# ISA_XILINX.net
KiCad netlist of a schematic drawn in Altium Designer
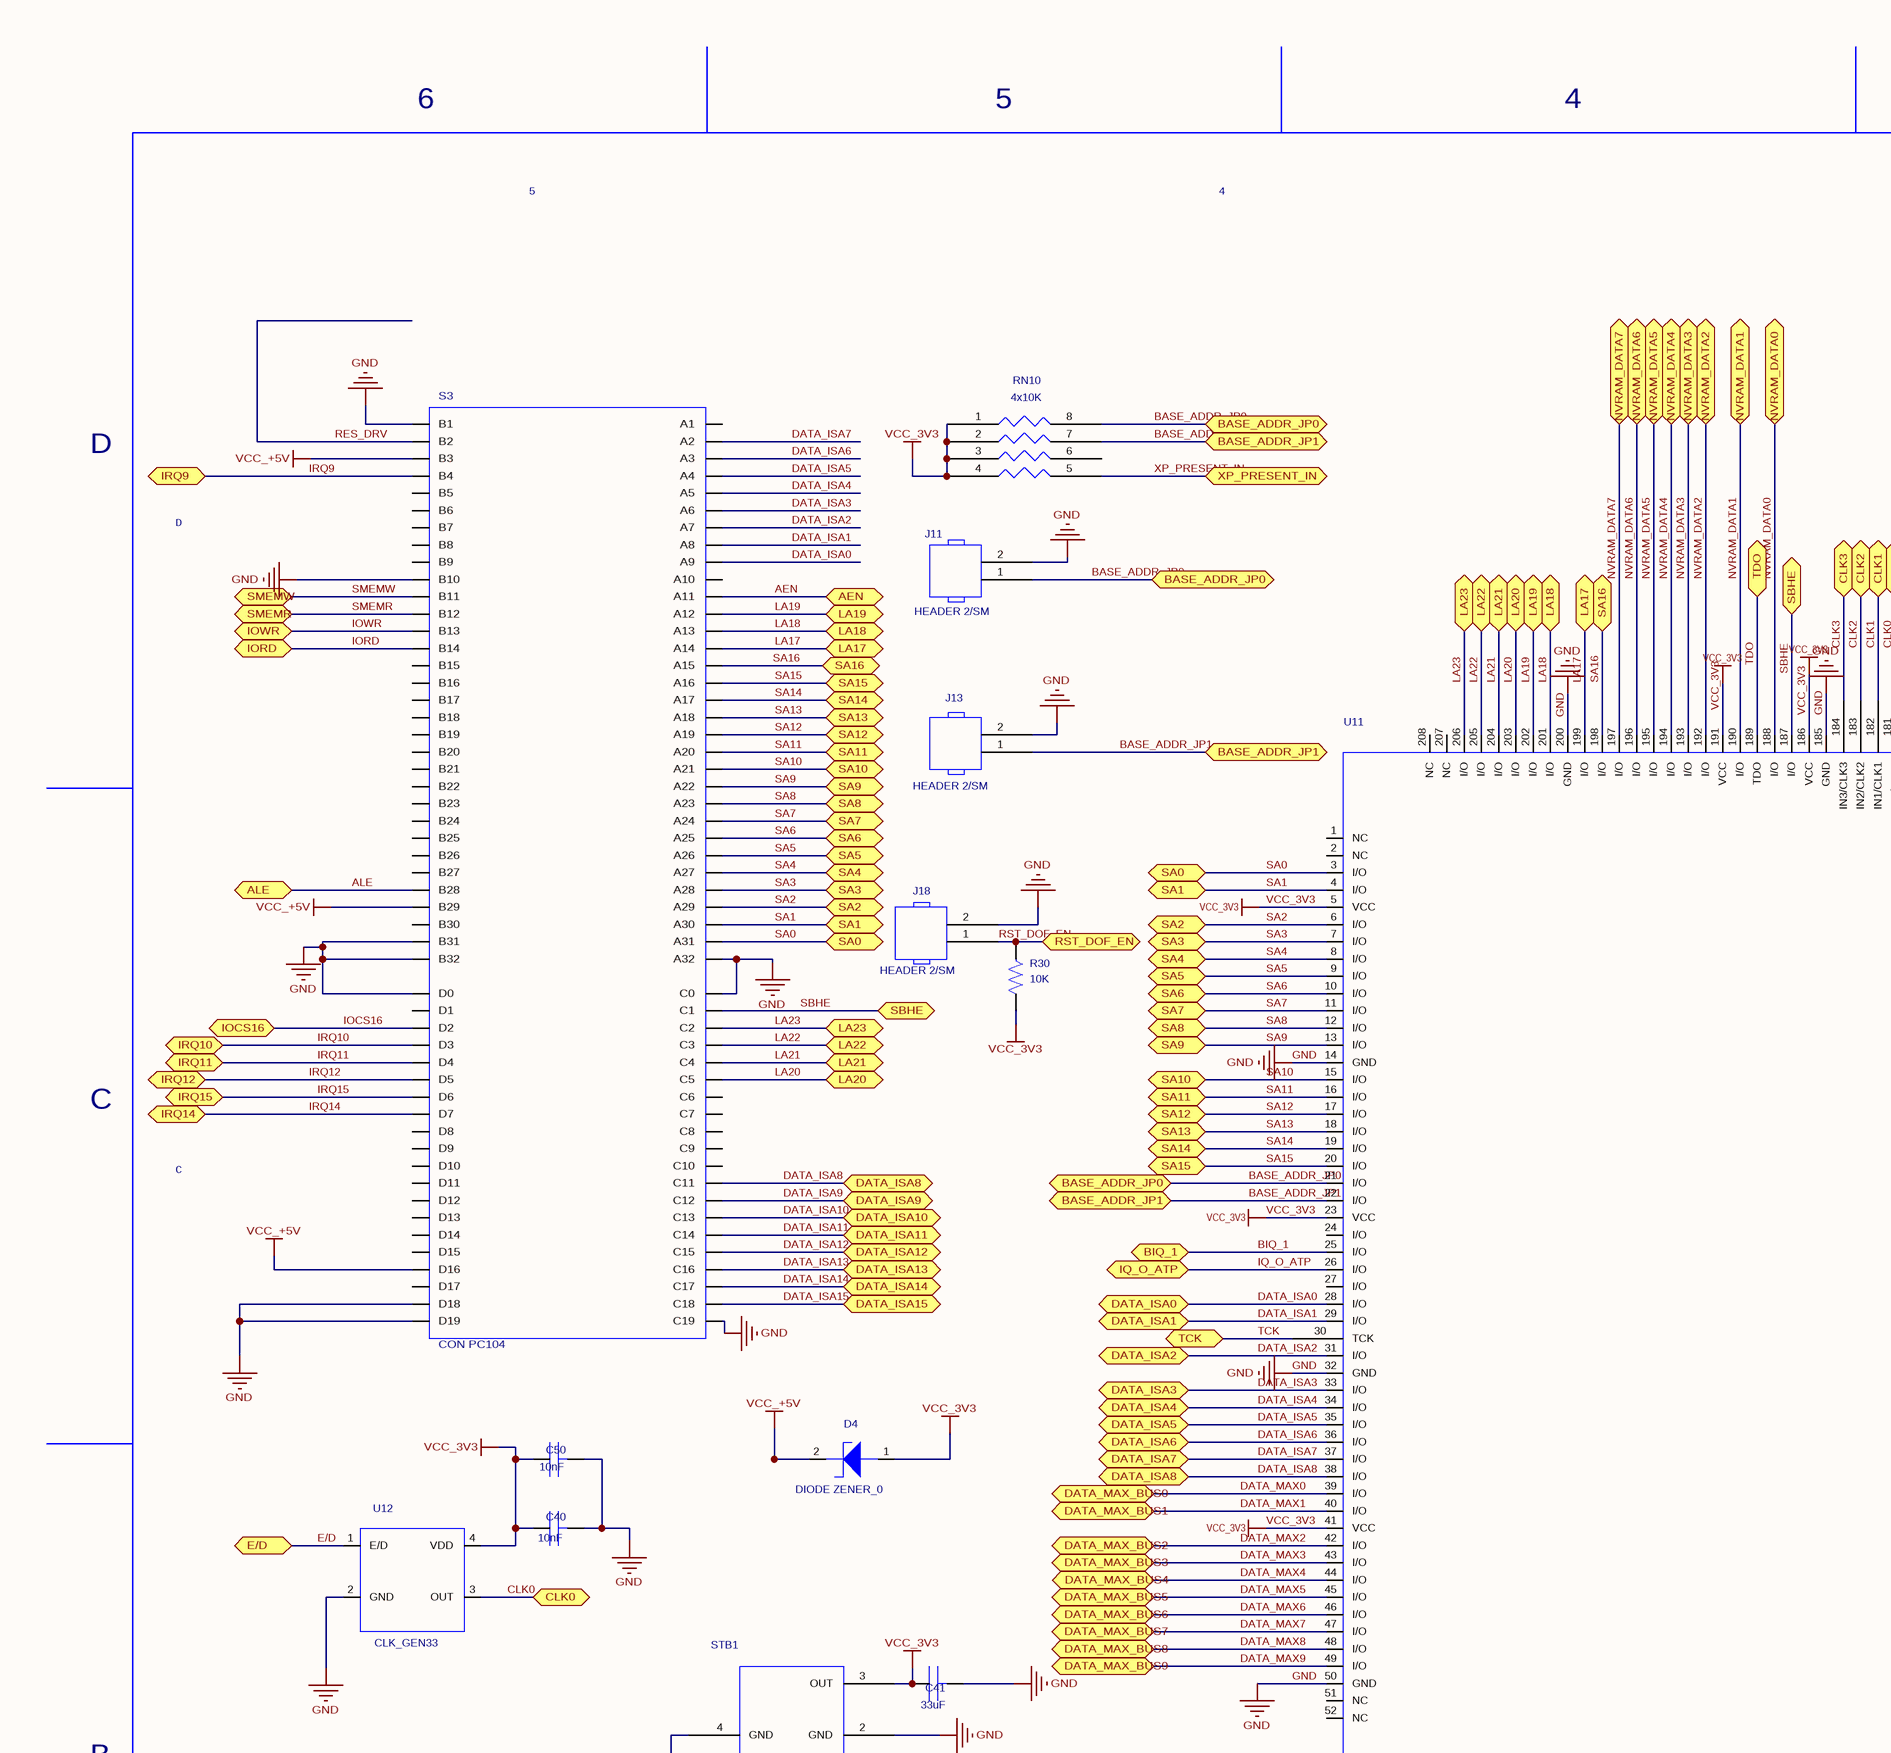
[diagram p0: ISA_XILINX.SchDoc, top left]
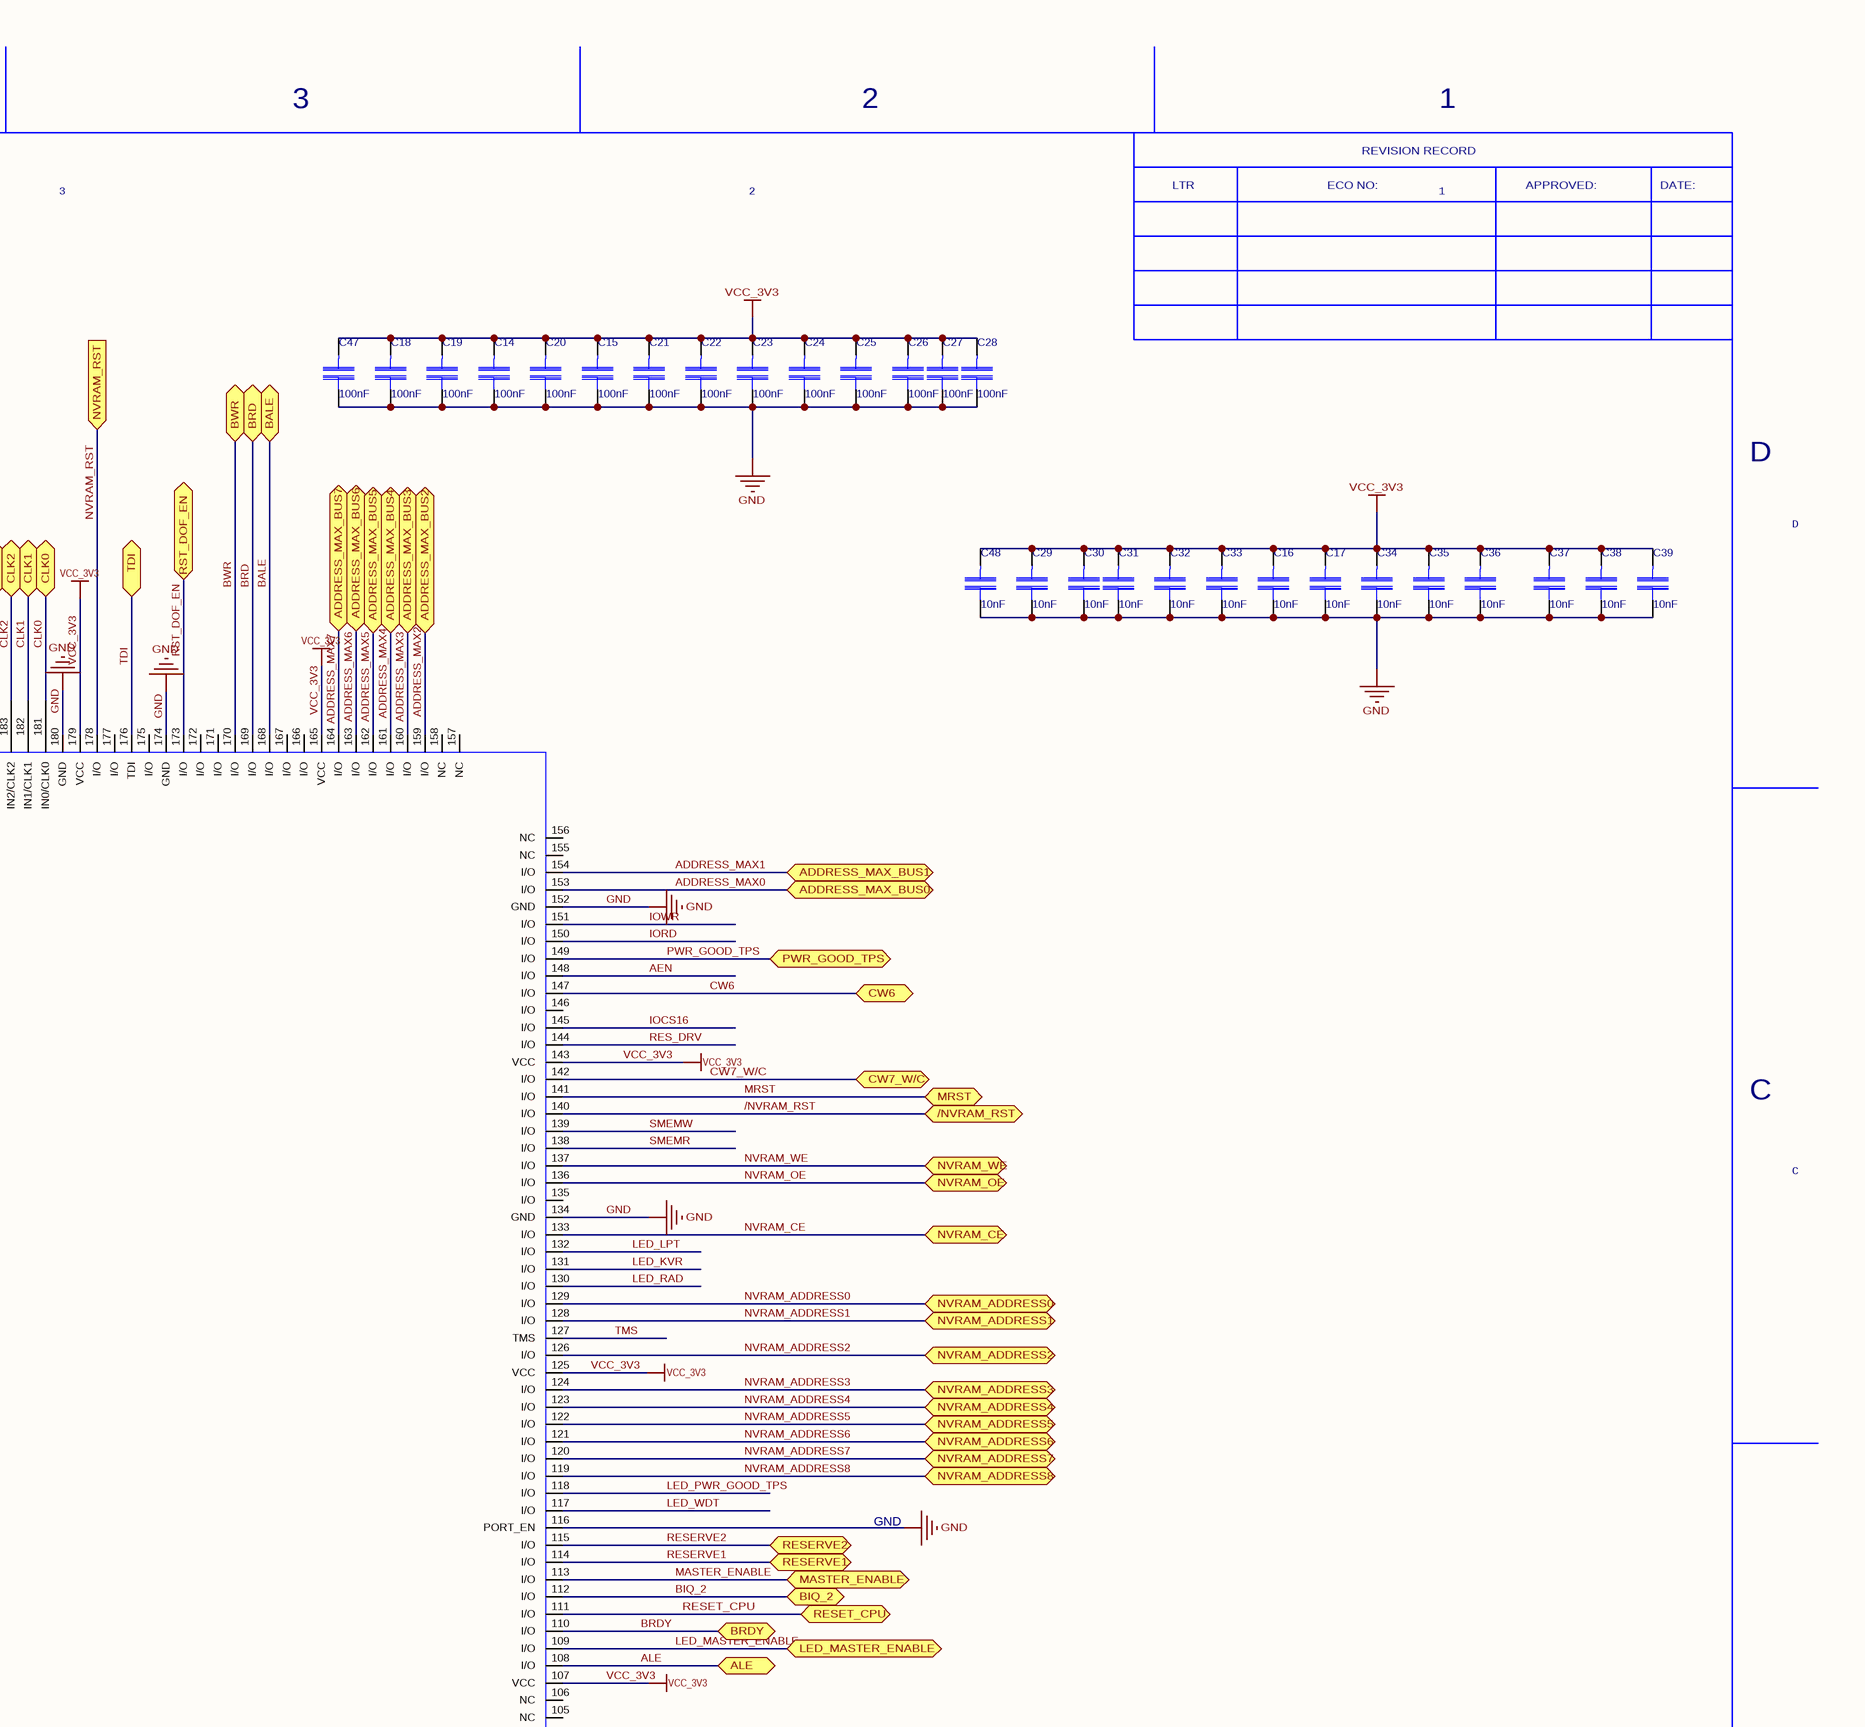
[diagram p1: ISA_XILINX.SchDoc, top right]
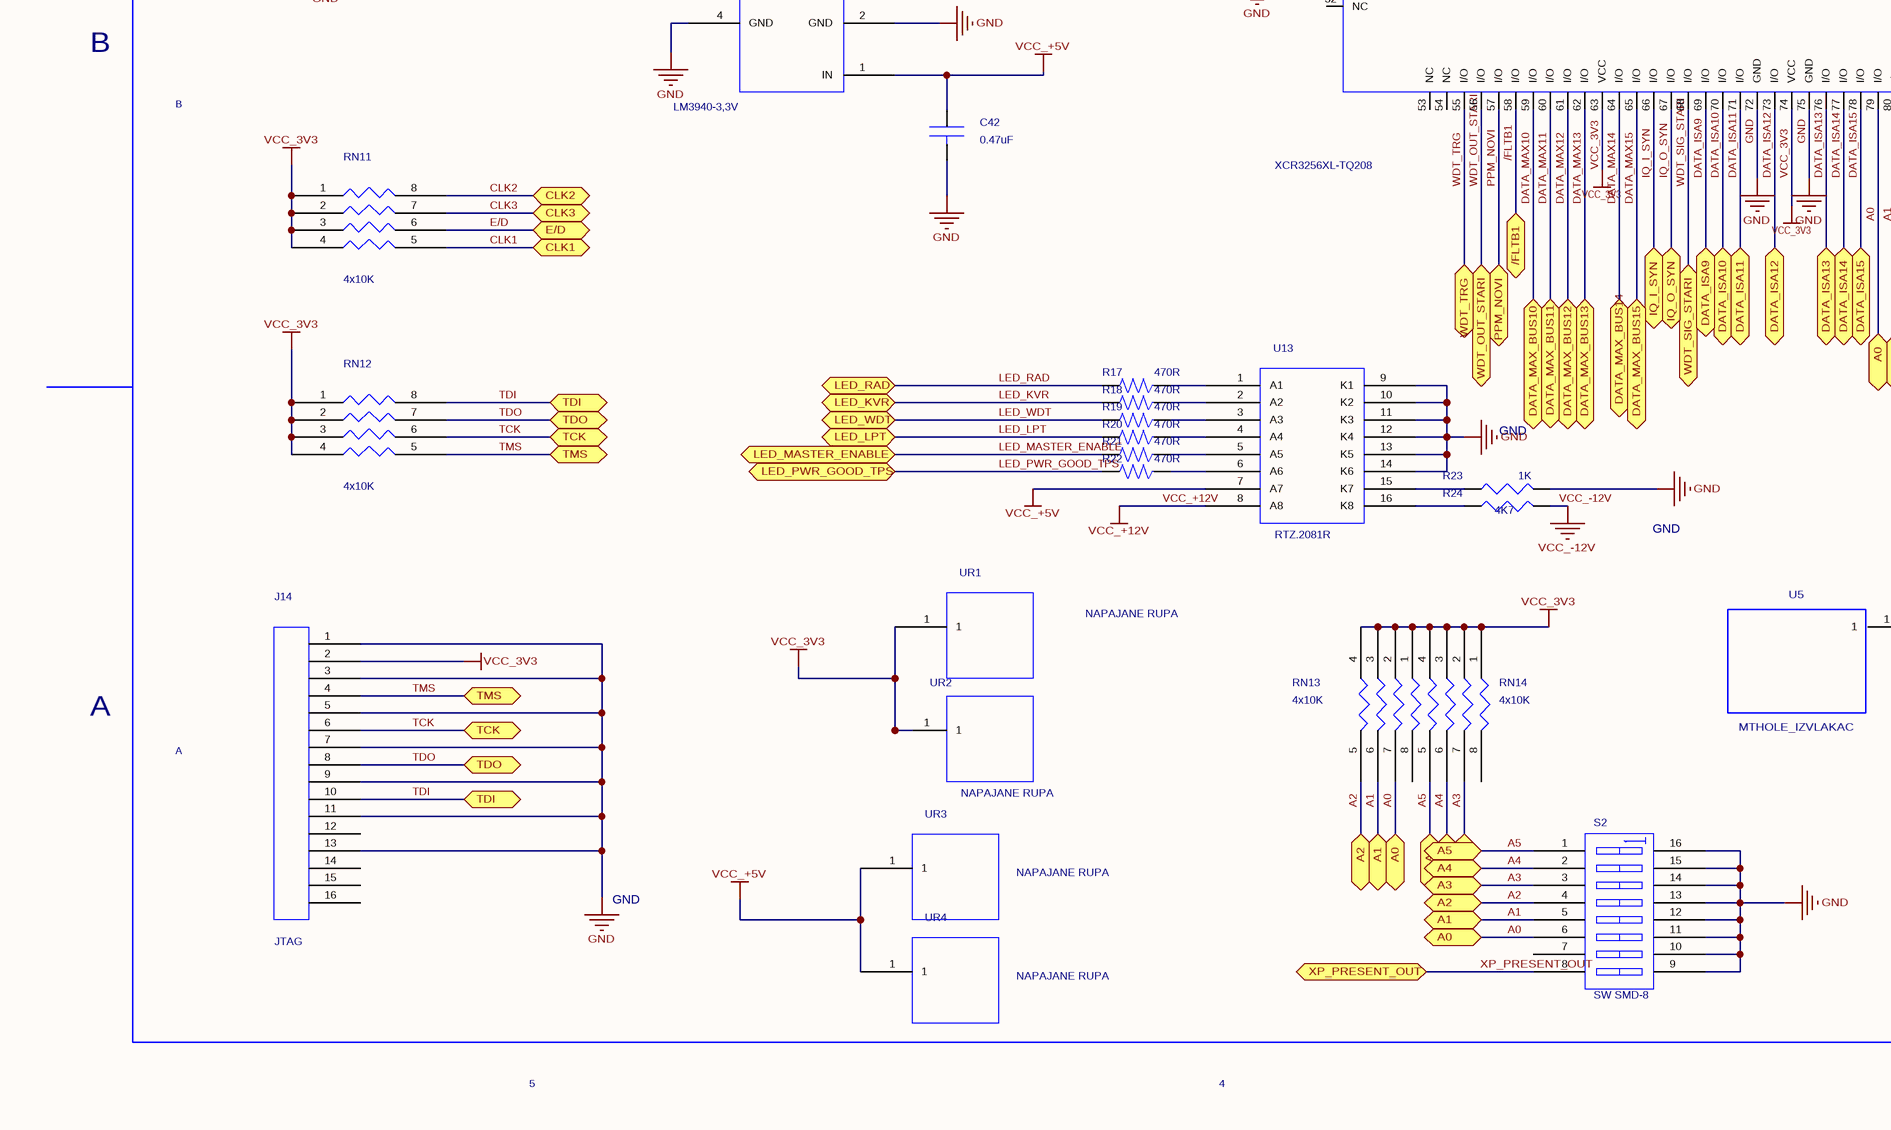
[diagram p2: ISA_XILINX.SchDoc, bottom left]
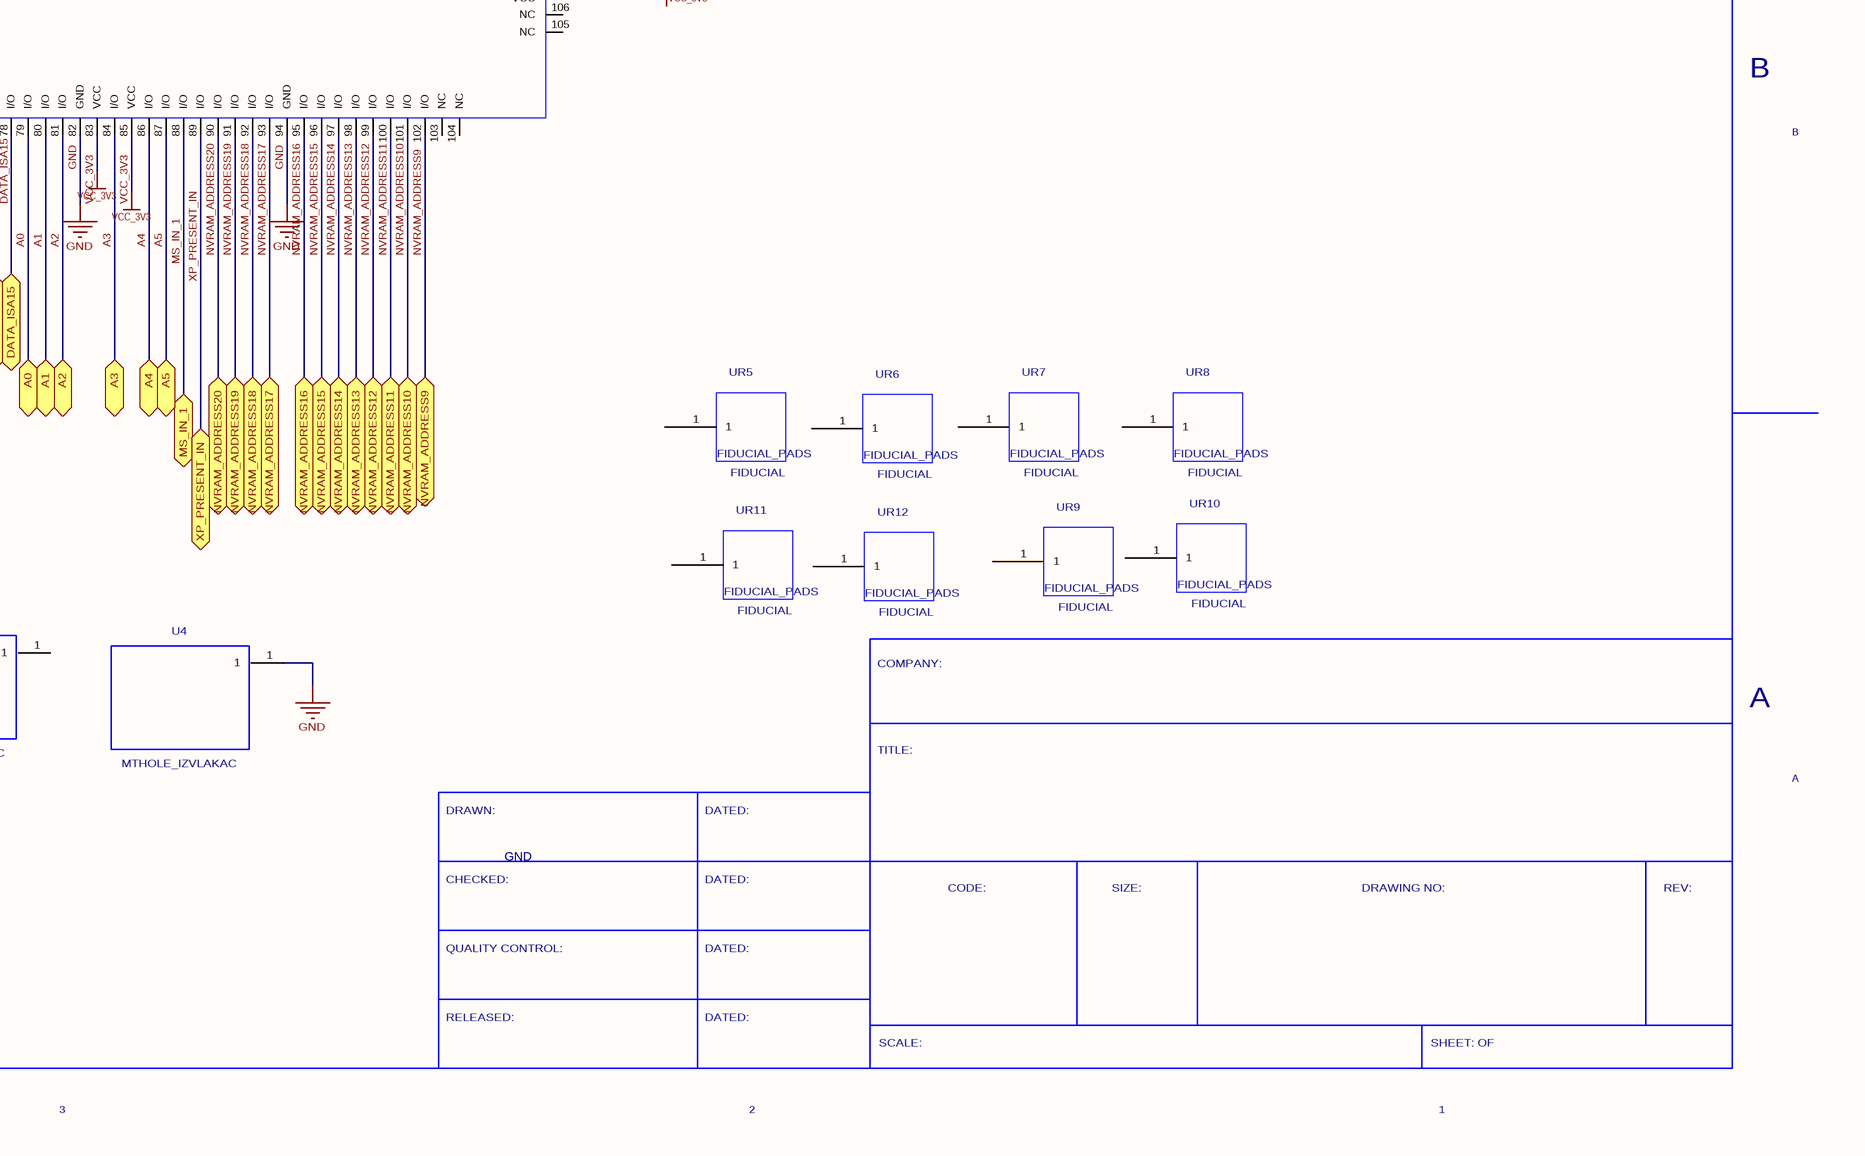
[diagram p3: ISA_XILINX.SchDoc, bottom right]

(export (version "E")
  (design (tool "Eeschema 10.0.6"))
  (components
    (comp (ref "C14")
      (value "100nF")
      (footprint "SM/C_0805")
      (fields (field (name "Comment") "C"))
      (libsource (lib "*") (part "C"))
    )
    (comp (ref "C15")
      (value "100nF")
      (footprint "SM/C_0805")
      (fields (field (name "Comment") "C"))
      (libsource (lib "*") (part "C"))
    )
    (comp (ref "C16")
      (value "10nF")
      (footprint "SM/C_0805")
      (fields (field (name "Comment") "C"))
      (libsource (lib "*") (part "C"))
    )
    (comp (ref "C17")
      (value "10nF")
      (footprint "SM/C_0805")
      (fields (field (name "Comment") "C"))
      (libsource (lib "*") (part "C"))
    )
    (comp (ref "C18")
      (value "100nF")
      (footprint "SM/C_0805")
      (fields (field (name "Comment") "C"))
      (libsource (lib "*") (part "C"))
    )
    (comp (ref "C19")
      (value "100nF")
      (footprint "SM/C_0805")
      (fields (field (name "Comment") "C"))
      (libsource (lib "*") (part "C"))
    )
    (comp (ref "C20")
      (value "100nF")
      (footprint "SM/C_0805")
      (fields (field (name "Comment") "C"))
      (libsource (lib "*") (part "C"))
    )
    (comp (ref "C21")
      (value "100nF")
      (footprint "SM/C_0805")
      (fields (field (name "Comment") "C"))
      (libsource (lib "*") (part "C"))
    )
    (comp (ref "C22")
      (value "100nF")
      (footprint "SM/C_0805")
      (fields (field (name "Comment") "C"))
      (libsource (lib "*") (part "C"))
    )
    (comp (ref "C23")
      (value "100nF")
      (footprint "SM/C_0805")
      (fields (field (name "Comment") "C"))
      (libsource (lib "*") (part "C"))
    )
    (comp (ref "C24")
      (value "100nF")
      (footprint "SM/C_0805")
      (fields (field (name "Comment") "C"))
      (libsource (lib "*") (part "C"))
    )
    (comp (ref "C25")
      (value "100nF")
      (footprint "SM/C_0805")
      (fields (field (name "Comment") "C"))
      (libsource (lib "*") (part "C"))
    )
    (comp (ref "C26")
      (value "100nF")
      (footprint "SM/C_0805")
      (fields (field (name "Comment") "C"))
      (libsource (lib "*") (part "C"))
    )
    (comp (ref "C27")
      (value "100nF")
      (footprint "SM/C_0805")
      (fields (field (name "Comment") "C"))
      (libsource (lib "*") (part "C"))
    )
    (comp (ref "C28")
      (value "100nF")
      (footprint "SM/C_0805")
      (fields (field (name "Comment") "C"))
      (libsource (lib "*") (part "C"))
    )
    (comp (ref "C29")
      (value "10nF")
      (footprint "SM/C_0805")
      (fields (field (name "Comment") "C"))
      (libsource (lib "*") (part "C"))
    )
    (comp (ref "C30")
      (value "10nF")
      (footprint "SM/C_0805")
      (fields (field (name "Comment") "C"))
      (libsource (lib "*") (part "C"))
    )
    (comp (ref "C31")
      (value "10nF")
      (footprint "SM/C_0805")
      (fields (field (name "Comment") "C"))
      (libsource (lib "*") (part "C"))
    )
    (comp (ref "C32")
      (value "10nF")
      (footprint "SM/C_0805")
      (fields (field (name "Comment") "C"))
      (libsource (lib "*") (part "C"))
    )
    (comp (ref "C33")
      (value "10nF")
      (footprint "SM/C_0805")
      (fields (field (name "Comment") "C"))
      (libsource (lib "*") (part "C"))
    )
    (comp (ref "C34")
      (value "10nF")
      (footprint "SM/C_0805")
      (fields (field (name "Comment") "C"))
      (libsource (lib "*") (part "C"))
    )
    (comp (ref "C35")
      (value "10nF")
      (footprint "SM/C_0805")
      (fields (field (name "Comment") "C"))
      (libsource (lib "*") (part "C"))
    )
    (comp (ref "C36")
      (value "10nF")
      (footprint "SM/C_0805")
      (fields (field (name "Comment") "C"))
      (libsource (lib "*") (part "C"))
    )
    (comp (ref "C37")
      (value "10nF")
      (footprint "SM/C_0805")
      (fields (field (name "Comment") "C"))
      (libsource (lib "*") (part "C"))
    )
    (comp (ref "C38")
      (value "10nF")
      (footprint "SM/C_0805")
      (fields (field (name "Comment") "C"))
      (libsource (lib "*") (part "C"))
    )
    (comp (ref "C39")
      (value "10nF")
      (footprint "SM/C_0805")
      (fields (field (name "Comment") "C"))
      (libsource (lib "*") (part "C"))
    )
    (comp (ref "C40")
      (value "10nF")
      (footprint "SM/C_0805")
      (fields (field (name "Comment") "C_4"))
      (libsource (lib "*") (part "C_4"))
    )
    (comp (ref "C41")
      (value "33uF")
      (footprint "CASE_D_MILOS")
      (fields (field (name "Comment") "C_4"))
      (libsource (lib "*") (part "C_4"))
    )
    (comp (ref "C42")
      (value "0.47uF")
      (footprint "CASE_B_MILOS")
      (fields (field (name "Comment") "C_4"))
      (libsource (lib "*") (part "C_4"))
    )
    (comp (ref "C47")
      (value "100nF")
      (footprint "SM/C_0805")
      (fields (field (name "Comment") "C"))
      (libsource (lib "*") (part "C"))
    )
    (comp (ref "C48")
      (value "10nF")
      (footprint "SM/C_0805")
      (fields (field (name "Comment") "C"))
      (libsource (lib "*") (part "C"))
    )
    (comp (ref "C50")
      (value "10nF")
      (footprint "SM/C_0805")
      (fields (field (name "Comment") "C_4"))
      (libsource (lib "*") (part "C_4"))
    )
    (comp (ref "D4")
      (value "DIODE ZENER_0")
      (footprint "BZV55-C3V3")
      (fields (field (name "Comment") "DIODE_ZENER_1"))
      (libsource (lib "*") (part "DIODE_ZENER_1"))
    )
    (comp (ref "J11")
      (value "HEADER 2/SM")
      (footprint "JUMPER_100")
      (fields (field (name "Comment") "HEADER_2/SM"))
      (libsource (lib "*") (part "HEADER_2/SM"))
    )
    (comp (ref "J13")
      (value "HEADER 2/SM")
      (footprint "JUMPER_100")
      (fields (field (name "Comment") "HEADER_2/SM"))
      (libsource (lib "*") (part "HEADER_2/SM"))
    )
    (comp (ref "J14")
      (value "JTAG")
      (footprint "JTAG_SMD_REV2")
      (fields (field (name "Comment") "CONN_FLEX_16/SM"))
      (libsource (lib "*") (part "CONN_FLEX_16/SM"))
    )
    (comp (ref "J18")
      (value "HEADER 2/SM")
      (footprint "JUMPER_100")
      (fields (field (name "Comment") "HEADER_2/SM"))
      (libsource (lib "*") (part "HEADER_2/SM"))
    )
    (comp (ref "R17")
      (value "470R")
      (footprint "SM/R_1206")
      (fields (field (name "VOLTAGE") "RVMAX") (field (name "POWER") "RMAX") (field (name "Comment") "R"))
      (libsource (lib "*") (part "R"))
    )
    (comp (ref "R18")
      (value "470R")
      (footprint "SM/R_1206")
      (fields (field (name "VOLTAGE") "RVMAX") (field (name "POWER") "RMAX") (field (name "Comment") "R"))
      (libsource (lib "*") (part "R"))
    )
    (comp (ref "R19")
      (value "470R")
      (footprint "SM/R_1206")
      (fields (field (name "VOLTAGE") "RVMAX") (field (name "POWER") "RMAX") (field (name "Comment") "R"))
      (libsource (lib "*") (part "R"))
    )
    (comp (ref "R20")
      (value "470R")
      (footprint "SM/R_1206")
      (fields (field (name "VOLTAGE") "RVMAX") (field (name "POWER") "RMAX") (field (name "Comment") "R"))
      (libsource (lib "*") (part "R"))
    )
    (comp (ref "R21")
      (value "470R")
      (footprint "SM/R_1206")
      (fields (field (name "VOLTAGE") "RVMAX") (field (name "POWER") "RMAX") (field (name "Comment") "R"))
      (libsource (lib "*") (part "R"))
    )
    (comp (ref "R22")
      (value "470R")
      (footprint "SM/R_1206")
      (fields (field (name "VOLTAGE") "RVMAX") (field (name "POWER") "RMAX") (field (name "Comment") "R"))
      (libsource (lib "*") (part "R"))
    )
    (comp (ref "R23")
      (value "1K")
      (footprint "SM/R_1206")
      (fields (field (name "Comment") "RESISTOR_2"))
      (libsource (lib "*") (part "RESISTOR_2"))
    )
    (comp (ref "R24")
      (value "4K7")
      (footprint "SM/R_1206")
      (fields (field (name "Comment") "RESISTOR_2"))
      (libsource (lib "*") (part "RESISTOR_2"))
    )
    (comp (ref "R30")
      (value "10K")
      (footprint "SM/R_1206")
      (fields (field (name "VOLTAGE") "RVMAX") (field (name "POWER") "RMAX") (field (name "Comment") "R"))
      (libsource (lib "*") (part "R"))
    )
    (comp (ref "RN10")
      (value "4x10K")
      (footprint "SMD_RX4")
      (fields (field (name "Comment") "RESAR_IS_4/SM"))
      (libsource (lib "*") (part "RESAR_IS_4/SM"))
    )
    (comp (ref "RN11")
      (value "4x10K")
      (footprint "SMD_RX4")
      (fields (field (name "Comment") "RESAR_IS_4/SM"))
      (libsource (lib "*") (part "RESAR_IS_4/SM"))
    )
    (comp (ref "RN12")
      (value "4x10K")
      (footprint "SMD_RX4")
      (fields (field (name "Comment") "RESAR_IS_4/SM"))
      (libsource (lib "*") (part "RESAR_IS_4/SM"))
    )
    (comp (ref "RN13")
      (value "4x10K")
      (footprint "SMD_RX4")
      (fields (field (name "Comment") "RESAR_IS_4/SM"))
      (libsource (lib "*") (part "RESAR_IS_4/SM"))
    )
    (comp (ref "RN14")
      (value "4x10K")
      (footprint "SMD_RX4")
      (fields (field (name "Comment") "RESAR_IS_4/SM"))
      (libsource (lib "*") (part "RESAR_IS_4/SM"))
    )
    (comp (ref "S2")
      (value "SW SMD-8")
      (footprint "SMD_DIPSW_100")
      (fields (field (name "Comment") "SW_DIP-8"))
      (libsource (lib "*") (part "SW_DIP-8"))
    )
    (comp (ref "S3")
      (value "CON PC104")
      (footprint "PC104_REV13")
      (fields (field (name "Comment") "CON_EISAE_0"))
      (libsource (lib "*") (part "CON_EISAE_0"))
    )
    (comp (ref "STB1")
      (value "LM3940-3,3V")
      (footprint "TO263AA_GND_PLANE_REV1")
      (fields (field (name "Comment") "LM3940-3_3V"))
      (libsource (lib "*") (part "LM3940-3_3V"))
    )
    (comp (ref "U4")
      (value "MTHOLE_IZVLAKAC")
      (footprint "MTH_IZVLAKAC_PADS")
      (description "Rupa za Rittal-ov izvlakac")
      (libsource (lib "*") (part "MTHOLE_IZVLAKAC"))
    )
    (comp (ref "U5")
      (value "MTHOLE_IZVLAKAC")
      (footprint "MTH_IZVLAKAC_PADS")
      (description "Rupa za Rittal-ov izvlakac")
      (libsource (lib "*") (part "MTHOLE_IZVLAKAC"))
    )
    (comp (ref "U11")
      (value "XCR3256XL-TQ208")
      (footprint "QUAD.50M/208/WG30.60")
      (libsource (lib "*") (part "XCR3256XL-TQ208"))
    )
    (comp (ref "U12")
      (value "CLK_GEN33")
      (footprint "CLK_GEN33_REV1")
      (libsource (lib "*") (part "CLK_GEN33"))
    )
    (comp (ref "U13")
      (value "RTZ.2081R")
      (footprint "LED_8_REV3_PADS")
      (description "LED8x1")
      (fields (field (name "Comment") "LED8X1"))
      (libsource (lib "*") (part "LED8X1"))
    )
    (comp (ref "UR1")
      (value "NAPAJANE RUPA")
      (footprint "NAPAJANJE_RUPA_REV1")
      (fields (field (name "Comment") "NAPAJANE_RUPA"))
      (libsource (lib "*") (part "NAPAJANE_RUPA"))
    )
    (comp (ref "UR2")
      (value "NAPAJANE RUPA")
      (footprint "NAPAJANJE_RUPA_REV1")
      (fields (field (name "Comment") "NAPAJANE_RUPA"))
      (libsource (lib "*") (part "NAPAJANE_RUPA"))
    )
    (comp (ref "UR3")
      (value "NAPAJANE RUPA")
      (footprint "NAPAJANJE_RUPA_REV1")
      (fields (field (name "Comment") "NAPAJANE_RUPA"))
      (libsource (lib "*") (part "NAPAJANE_RUPA"))
    )
    (comp (ref "UR4")
      (value "NAPAJANE RUPA")
      (footprint "NAPAJANJE_RUPA_REV1")
      (fields (field (name "Comment") "NAPAJANE_RUPA"))
      (libsource (lib "*") (part "NAPAJANE_RUPA"))
    )
    (comp (ref "UR5")
      (value "FIDUCIAL_PADS")
      (footprint "FIDUCIAL_R_TOP")
      (fields (field (name "ALTIUM_VALUE") "FIDUCIAL"))
      (libsource (lib "*") (part "FIDUCIAL_PADS"))
    )
    (comp (ref "UR6")
      (value "FIDUCIAL_PADS")
      (footprint "FIDUCIAL_R_TOP")
      (fields (field (name "ALTIUM_VALUE") "FIDUCIAL"))
      (libsource (lib "*") (part "FIDUCIAL_PADS"))
    )
    (comp (ref "UR7")
      (value "FIDUCIAL_PADS")
      (footprint "FIDUCIAL_R_TOP")
      (fields (field (name "ALTIUM_VALUE") "FIDUCIAL"))
      (libsource (lib "*") (part "FIDUCIAL_PADS"))
    )
    (comp (ref "UR8")
      (value "FIDUCIAL_PADS")
      (footprint "FIDUCIAL_R_TOP")
      (fields (field (name "ALTIUM_VALUE") "FIDUCIAL"))
      (libsource (lib "*") (part "FIDUCIAL_PADS"))
    )
    (comp (ref "UR9")
      (value "FIDUCIAL_PADS")
      (footprint "FIDUCIAL_R_TOP")
      (fields (field (name "ALTIUM_VALUE") "FIDUCIAL"))
      (libsource (lib "*") (part "FIDUCIAL_PADS"))
    )
    (comp (ref "UR10")
      (value "FIDUCIAL_PADS")
      (footprint "FIDUCIAL_R_TOP")
      (fields (field (name "ALTIUM_VALUE") "FIDUCIAL"))
      (libsource (lib "*") (part "FIDUCIAL_PADS"))
    )
    (comp (ref "UR11")
      (value "FIDUCIAL_PADS")
      (footprint "FIDUCIAL_R_TOP")
      (fields (field (name "ALTIUM_VALUE") "FIDUCIAL"))
      (libsource (lib "*") (part "FIDUCIAL_PADS"))
    )
    (comp (ref "UR12")
      (value "FIDUCIAL_PADS")
      (footprint "FIDUCIAL_R_TOP")
      (fields (field (name "ALTIUM_VALUE") "FIDUCIAL"))
      (libsource (lib "*") (part "FIDUCIAL_PADS"))
    )
  )
  (nets
    (net (code "1") (name "/A0") (class "Default")
      (node (ref "RN13") (pin "7") (pinfunction "7_7") (pintype "passive"))
      (node (ref "S2") (pin "6") (pinfunction "A6_6") (pintype "passive"))
      (node (ref "U11") (pin "79") (pinfunction "I/O_79") (pintype "bidirectional"))
    )
    (net (code "2") (name "/A1") (class "Default")
      (node (ref "RN13") (pin "6") (pinfunction "6_6") (pintype "passive"))
      (node (ref "S2") (pin "5") (pinfunction "A5_5") (pintype "passive"))
      (node (ref "U11") (pin "80") (pinfunction "I/O_80") (pintype "bidirectional"))
    )
    (net (code "3") (name "/A2") (class "Default")
      (node (ref "RN13") (pin "5") (pinfunction "5_5") (pintype "passive"))
      (node (ref "S2") (pin "4") (pinfunction "A4_4") (pintype "passive"))
      (node (ref "U11") (pin "81") (pinfunction "I/O_81") (pintype "bidirectional"))
    )
    (net (code "4") (name "/A3") (class "Default")
      (node (ref "RN14") (pin "7") (pinfunction "7_7") (pintype "passive"))
      (node (ref "S2") (pin "3") (pinfunction "A3_3") (pintype "passive"))
      (node (ref "U11") (pin "84") (pinfunction "I/O_84") (pintype "bidirectional"))
    )
    (net (code "5") (name "/A4") (class "Default")
      (node (ref "RN14") (pin "6") (pinfunction "6_6") (pintype "passive"))
      (node (ref "S2") (pin "2") (pinfunction "A2_2") (pintype "passive"))
      (node (ref "U11") (pin "86") (pinfunction "I/O_86") (pintype "bidirectional"))
    )
    (net (code "6") (name "/A5") (class "Default")
      (node (ref "RN14") (pin "5") (pinfunction "5_5") (pintype "passive"))
      (node (ref "S2") (pin "1") (pinfunction "A1_1") (pintype "passive"))
      (node (ref "U11") (pin "87") (pinfunction "I/O_87") (pintype "bidirectional"))
    )
    (net (code "7") (name "/ADDRESS_MAX0") (class "Default")
      (node (ref "U11") (pin "153") (pinfunction "I/O_153") (pintype "bidirectional"))
    )
    (net (code "8") (name "/ADDRESS_MAX1") (class "Default")
      (node (ref "U11") (pin "154") (pinfunction "I/O_154") (pintype "bidirectional"))
    )
    (net (code "9") (name "/ADDRESS_MAX2") (class "Default")
      (node (ref "U11") (pin "159") (pinfunction "I/O_159") (pintype "bidirectional"))
    )
    (net (code "10") (name "/ADDRESS_MAX3") (class "Default")
      (node (ref "U11") (pin "160") (pinfunction "I/O_160") (pintype "bidirectional"))
    )
    (net (code "11") (name "/ADDRESS_MAX4") (class "Default")
      (node (ref "U11") (pin "161") (pinfunction "I/O_161") (pintype "bidirectional"))
    )
    (net (code "12") (name "/ADDRESS_MAX5") (class "Default")
      (node (ref "U11") (pin "162") (pinfunction "I/O_162") (pintype "bidirectional"))
    )
    (net (code "13") (name "/ADDRESS_MAX6") (class "Default")
      (node (ref "U11") (pin "163") (pinfunction "I/O_163") (pintype "bidirectional"))
    )
    (net (code "14") (name "/ADDRESS_MAX7") (class "Default")
      (node (ref "U11") (pin "164") (pinfunction "I/O_164") (pintype "bidirectional"))
    )
    (net (code "15") (name "/AEN") (class "Default")
      (node (ref "S3") (pin "A11") (pinfunction "A11_A11") (pintype "passive"))
      (node (ref "U11") (pin "148") (pinfunction "I/O_148") (pintype "bidirectional"))
    )
    (net (code "16") (name "/ALE") (class "Default")
      (node (ref "S3") (pin "B28") (pinfunction "B28_B28") (pintype "passive"))
      (node (ref "U11") (pin "108") (pinfunction "I/O_108") (pintype "bidirectional"))
    )
    (net (code "17") (name "/BALE") (class "Default")
      (node (ref "U11") (pin "168") (pinfunction "I/O_168") (pintype "bidirectional"))
    )
    (net (code "18") (name "/BASE_ADDR_JP0") (class "Default")
      (node (ref "J11") (pin "1") (pinfunction "1_1") (pintype "passive"))
      (node (ref "RN10") (pin "8") (pinfunction "8_8") (pintype "passive"))
      (node (ref "U11") (pin "21") (pinfunction "I/O_21") (pintype "bidirectional"))
    )
    (net (code "19") (name "/BASE_ADDR_JP1") (class "Default")
      (node (ref "J13") (pin "1") (pinfunction "1_1") (pintype "passive"))
      (node (ref "RN10") (pin "7") (pinfunction "7_7") (pintype "passive"))
      (node (ref "U11") (pin "22") (pinfunction "I/O_22") (pintype "bidirectional"))
    )
    (net (code "20") (name "/BIQ_1") (class "Default")
      (node (ref "U11") (pin "25") (pinfunction "I/O_25") (pintype "bidirectional"))
    )
    (net (code "21") (name "/BIQ_2") (class "Default")
      (node (ref "U11") (pin "112") (pinfunction "I/O_112") (pintype "bidirectional"))
    )
    (net (code "22") (name "/BRD") (class "Default")
      (node (ref "U11") (pin "169") (pinfunction "I/O_169") (pintype "bidirectional"))
    )
    (net (code "23") (name "/BRDY") (class "Default")
      (node (ref "U11") (pin "110") (pinfunction "I/O_110") (pintype "bidirectional"))
    )
    (net (code "24") (name "/BWR") (class "Default")
      (node (ref "U11") (pin "170") (pinfunction "I/O_170") (pintype "bidirectional"))
    )
    (net (code "25") (name "/CLK0") (class "Default")
      (node (ref "U11") (pin "181") (pinfunction "IN0/CLK0_181") (pintype "passive"))
      (node (ref "U12") (pin "3") (pinfunction "OUT_3") (pintype "passive"))
    )
    (net (code "26") (name "/CLK1") (class "Default")
      (node (ref "RN11") (pin "5") (pinfunction "5_5") (pintype "passive"))
      (node (ref "U11") (pin "182") (pinfunction "IN1/CLK1_182") (pintype "passive"))
    )
    (net (code "27") (name "/CLK2") (class "Default")
      (node (ref "RN11") (pin "8") (pinfunction "8_8") (pintype "passive"))
      (node (ref "U11") (pin "183") (pinfunction "IN2/CLK2_183") (pintype "passive"))
    )
    (net (code "28") (name "/CLK3") (class "Default")
      (node (ref "RN11") (pin "7") (pinfunction "7_7") (pintype "passive"))
      (node (ref "U11") (pin "184") (pinfunction "IN3/CLK3_184") (pintype "passive"))
    )
    (net (code "29") (name "/CW6") (class "Default")
      (node (ref "U11") (pin "147") (pinfunction "I/O_147") (pintype "bidirectional"))
    )
    (net (code "30") (name "/CW7_W{slash}C") (class "Default")
      (node (ref "U11") (pin "142") (pinfunction "I/O_142") (pintype "bidirectional"))
    )
    (net (code "31") (name "/DATA_ISA0") (class "Default")
      (node (ref "S3") (pin "A9") (pinfunction "A9_A9") (pintype "passive"))
      (node (ref "U11") (pin "28") (pinfunction "I/O_28") (pintype "bidirectional"))
    )
    (net (code "32") (name "/DATA_ISA1") (class "Default")
      (node (ref "S3") (pin "A8") (pinfunction "A8_A8") (pintype "passive"))
      (node (ref "U11") (pin "29") (pinfunction "I/O_29") (pintype "bidirectional"))
    )
    (net (code "33") (name "/DATA_ISA2") (class "Default")
      (node (ref "S3") (pin "A7") (pinfunction "A7_A7") (pintype "passive"))
      (node (ref "U11") (pin "31") (pinfunction "I/O_31") (pintype "bidirectional"))
    )
    (net (code "34") (name "/DATA_ISA3") (class "Default")
      (node (ref "S3") (pin "A6") (pinfunction "A6_A6") (pintype "passive"))
      (node (ref "U11") (pin "33") (pinfunction "I/O_33") (pintype "bidirectional"))
    )
    (net (code "35") (name "/DATA_ISA4") (class "Default")
      (node (ref "S3") (pin "A5") (pinfunction "A5_A5") (pintype "passive"))
      (node (ref "U11") (pin "34") (pinfunction "I/O_34") (pintype "bidirectional"))
    )
    (net (code "36") (name "/DATA_ISA5") (class "Default")
      (node (ref "S3") (pin "A4") (pinfunction "A4_A4") (pintype "passive"))
      (node (ref "U11") (pin "35") (pinfunction "I/O_35") (pintype "bidirectional"))
    )
    (net (code "37") (name "/DATA_ISA6") (class "Default")
      (node (ref "S3") (pin "A3") (pinfunction "A3_A3") (pintype "passive"))
      (node (ref "U11") (pin "36") (pinfunction "I/O_36") (pintype "bidirectional"))
    )
    (net (code "38") (name "/DATA_ISA7") (class "Default")
      (node (ref "S3") (pin "A2") (pinfunction "A2_A2") (pintype "passive"))
      (node (ref "U11") (pin "37") (pinfunction "I/O_37") (pintype "bidirectional"))
    )
    (net (code "39") (name "/DATA_ISA8") (class "Default")
      (node (ref "S3") (pin "C11") (pinfunction "C11_C11") (pintype "passive"))
      (node (ref "U11") (pin "38") (pinfunction "I/O_38") (pintype "bidirectional"))
    )
    (net (code "40") (name "/DATA_ISA9") (class "Default")
      (node (ref "S3") (pin "C12") (pinfunction "C12_C12") (pintype "passive"))
      (node (ref "U11") (pin "69") (pinfunction "I/O_69") (pintype "bidirectional"))
    )
    (net (code "41") (name "/DATA_ISA10") (class "Default")
      (node (ref "S3") (pin "C13") (pinfunction "C13_C13") (pintype "passive"))
      (node (ref "U11") (pin "70") (pinfunction "I/O_70") (pintype "bidirectional"))
    )
    (net (code "42") (name "/DATA_ISA11") (class "Default")
      (node (ref "S3") (pin "C14") (pinfunction "C14_C14") (pintype "passive"))
      (node (ref "U11") (pin "71") (pinfunction "I/O_71") (pintype "bidirectional"))
    )
    (net (code "43") (name "/DATA_ISA12") (class "Default")
      (node (ref "S3") (pin "C15") (pinfunction "C15_C15") (pintype "passive"))
      (node (ref "U11") (pin "73") (pinfunction "I/O_73") (pintype "bidirectional"))
    )
    (net (code "44") (name "/DATA_ISA13") (class "Default")
      (node (ref "S3") (pin "C16") (pinfunction "C16_C16") (pintype "passive"))
      (node (ref "U11") (pin "76") (pinfunction "I/O_76") (pintype "bidirectional"))
    )
    (net (code "45") (name "/DATA_ISA14") (class "Default")
      (node (ref "S3") (pin "C17") (pinfunction "C17_C17") (pintype "passive"))
      (node (ref "U11") (pin "77") (pinfunction "I/O_77") (pintype "bidirectional"))
    )
    (net (code "46") (name "/DATA_ISA15") (class "Default")
      (node (ref "S3") (pin "C18") (pinfunction "C18_C18") (pintype "passive"))
      (node (ref "U11") (pin "78") (pinfunction "I/O_78") (pintype "bidirectional"))
    )
    (net (code "47") (name "/DATA_MAX0") (class "Default")
      (node (ref "U11") (pin "39") (pinfunction "I/O_39") (pintype "bidirectional"))
    )
    (net (code "48") (name "/DATA_MAX1") (class "Default")
      (node (ref "U11") (pin "40") (pinfunction "I/O_40") (pintype "bidirectional"))
    )
    (net (code "49") (name "/DATA_MAX2") (class "Default")
      (node (ref "U11") (pin "42") (pinfunction "I/O_42") (pintype "bidirectional"))
    )
    (net (code "50") (name "/DATA_MAX3") (class "Default")
      (node (ref "U11") (pin "43") (pinfunction "I/O_43") (pintype "bidirectional"))
    )
    (net (code "51") (name "/DATA_MAX4") (class "Default")
      (node (ref "U11") (pin "44") (pinfunction "I/O_44") (pintype "bidirectional"))
    )
    (net (code "52") (name "/DATA_MAX5") (class "Default")
      (node (ref "U11") (pin "45") (pinfunction "I/O_45") (pintype "bidirectional"))
    )
    (net (code "53") (name "/DATA_MAX6") (class "Default")
      (node (ref "U11") (pin "46") (pinfunction "I/O_46") (pintype "bidirectional"))
    )
    (net (code "54") (name "/DATA_MAX7") (class "Default")
      (node (ref "U11") (pin "47") (pinfunction "I/O_47") (pintype "bidirectional"))
    )
    (net (code "55") (name "/DATA_MAX8") (class "Default")
      (node (ref "U11") (pin "48") (pinfunction "I/O_48") (pintype "bidirectional"))
    )
    (net (code "56") (name "/DATA_MAX9") (class "Default")
      (node (ref "U11") (pin "49") (pinfunction "I/O_49") (pintype "bidirectional"))
    )
    (net (code "57") (name "/DATA_MAX10") (class "Default")
      (node (ref "U11") (pin "59") (pinfunction "I/O_59") (pintype "bidirectional"))
    )
    (net (code "58") (name "/DATA_MAX11") (class "Default")
      (node (ref "U11") (pin "60") (pinfunction "I/O_60") (pintype "bidirectional"))
    )
    (net (code "59") (name "/DATA_MAX12") (class "Default")
      (node (ref "U11") (pin "61") (pinfunction "I/O_61") (pintype "bidirectional"))
    )
    (net (code "60") (name "/DATA_MAX13") (class "Default")
      (node (ref "U11") (pin "62") (pinfunction "I/O_62") (pintype "bidirectional"))
    )
    (net (code "61") (name "/DATA_MAX14") (class "Default")
      (node (ref "U11") (pin "64") (pinfunction "I/O_64") (pintype "bidirectional"))
    )
    (net (code "62") (name "/DATA_MAX15") (class "Default")
      (node (ref "U11") (pin "65") (pinfunction "I/O_65") (pintype "bidirectional"))
    )
    (net (code "63") (name "/E{slash}D") (class "Default")
      (node (ref "RN11") (pin "6") (pinfunction "6_6") (pintype "passive"))
      (node (ref "U12") (pin "1") (pinfunction "E/D_1") (pintype "passive"))
    )
    (net (code "64") (name "/IOCS16") (class "Default")
      (node (ref "S3") (pin "D2") (pinfunction "D2_D2") (pintype "passive"))
      (node (ref "U11") (pin "145") (pinfunction "I/O_145") (pintype "bidirectional"))
    )
    (net (code "65") (name "/IORD") (class "Default")
      (node (ref "S3") (pin "B14") (pinfunction "B14_B14") (pintype "passive"))
      (node (ref "U11") (pin "150") (pinfunction "I/O_150") (pintype "bidirectional"))
    )
    (net (code "66") (name "/IOWR") (class "Default")
      (node (ref "S3") (pin "B13") (pinfunction "B13_B13") (pintype "passive"))
      (node (ref "U11") (pin "151") (pinfunction "I/O_151") (pintype "bidirectional"))
    )
    (net (code "67") (name "/IQ_I_SYN") (class "Default")
      (node (ref "U11") (pin "66") (pinfunction "I/O_66") (pintype "bidirectional"))
    )
    (net (code "68") (name "/IQ_O_ATP") (class "Default")
      (node (ref "U11") (pin "26") (pinfunction "I/O_26") (pintype "bidirectional"))
    )
    (net (code "69") (name "/IQ_O_SYN") (class "Default")
      (node (ref "U11") (pin "67") (pinfunction "I/O_67") (pintype "bidirectional"))
    )
    (net (code "70") (name "/IRQ9") (class "Default")
      (node (ref "S3") (pin "B4") (pinfunction "B4_B4") (pintype "passive"))
    )
    (net (code "71") (name "/IRQ10") (class "Default")
      (node (ref "S3") (pin "D3") (pinfunction "D3_D3") (pintype "passive"))
    )
    (net (code "72") (name "/IRQ11") (class "Default")
      (node (ref "S3") (pin "D4") (pinfunction "D4_D4") (pintype "passive"))
    )
    (net (code "73") (name "/IRQ12") (class "Default")
      (node (ref "S3") (pin "D5") (pinfunction "D5_D5") (pintype "passive"))
    )
    (net (code "74") (name "/IRQ14") (class "Default")
      (node (ref "S3") (pin "D7") (pinfunction "D7_D7") (pintype "passive"))
    )
    (net (code "75") (name "/IRQ15") (class "Default")
      (node (ref "S3") (pin "D6") (pinfunction "D6_D6") (pintype "passive"))
    )
    (net (code "76") (name "/LA17") (class "Default")
      (node (ref "S3") (pin "A14") (pinfunction "A14_A14") (pintype "passive"))
      (node (ref "U11") (pin "199") (pinfunction "I/O_199") (pintype "bidirectional"))
    )
    (net (code "77") (name "/LA18") (class "Default")
      (node (ref "S3") (pin "A13") (pinfunction "A13_A13") (pintype "passive"))
      (node (ref "U11") (pin "201") (pinfunction "I/O_201") (pintype "bidirectional"))
    )
    (net (code "78") (name "/LA19") (class "Default")
      (node (ref "S3") (pin "A12") (pinfunction "A12_A12") (pintype "passive"))
      (node (ref "U11") (pin "202") (pinfunction "I/O_202") (pintype "bidirectional"))
    )
    (net (code "79") (name "/LA20") (class "Default")
      (node (ref "S3") (pin "C5") (pinfunction "C5_C5") (pintype "passive"))
      (node (ref "U11") (pin "203") (pinfunction "I/O_203") (pintype "bidirectional"))
    )
    (net (code "80") (name "/LA21") (class "Default")
      (node (ref "S3") (pin "C4") (pinfunction "C4_C4") (pintype "passive"))
      (node (ref "U11") (pin "204") (pinfunction "I/O_204") (pintype "bidirectional"))
    )
    (net (code "81") (name "/LA22") (class "Default")
      (node (ref "S3") (pin "C3") (pinfunction "C3_C3") (pintype "passive"))
      (node (ref "U11") (pin "205") (pinfunction "I/O_205") (pintype "bidirectional"))
    )
    (net (code "82") (name "/LA23") (class "Default")
      (node (ref "S3") (pin "C2") (pinfunction "C2_C2") (pintype "passive"))
      (node (ref "U11") (pin "206") (pinfunction "I/O_206") (pintype "bidirectional"))
    )
    (net (code "83") (name "/LED_KVR") (class "Default")
      (node (ref "R18") (pin "2") (pinfunction "2_2") (pintype "passive"))
      (node (ref "U11") (pin "131") (pinfunction "I/O_131") (pintype "bidirectional"))
    )
    (net (code "84") (name "/LED_LPT") (class "Default")
      (node (ref "R20") (pin "2") (pinfunction "2_2") (pintype "passive"))
      (node (ref "U11") (pin "132") (pinfunction "I/O_132") (pintype "bidirectional"))
    )
    (net (code "85") (name "/LED_MASTER_ENABLE") (class "Default")
      (node (ref "R21") (pin "2") (pinfunction "2_2") (pintype "passive"))
      (node (ref "U11") (pin "109") (pinfunction "I/O_109") (pintype "bidirectional"))
    )
    (net (code "86") (name "/LED_PWR_GOOD_TPS") (class "Default")
      (node (ref "R22") (pin "2") (pinfunction "2_2") (pintype "passive"))
      (node (ref "U11") (pin "118") (pinfunction "I/O_118") (pintype "bidirectional"))
    )
    (net (code "87") (name "/LED_RAD") (class "Default")
      (node (ref "R17") (pin "2") (pinfunction "2_2") (pintype "passive"))
      (node (ref "U11") (pin "130") (pinfunction "I/O_130") (pintype "bidirectional"))
    )
    (net (code "88") (name "/LED_WDT") (class "Default")
      (node (ref "R19") (pin "2") (pinfunction "2_2") (pintype "passive"))
      (node (ref "U11") (pin "117") (pinfunction "I/O_117") (pintype "bidirectional"))
    )
    (net (code "89") (name "/MASTER_ENABLE") (class "Default")
      (node (ref "U11") (pin "113") (pinfunction "I/O_113") (pintype "bidirectional"))
    )
    (net (code "90") (name "/MRST") (class "Default")
      (node (ref "U11") (pin "141") (pinfunction "I/O_141") (pintype "bidirectional"))
    )
    (net (code "91") (name "/MS_IN_1") (class "Default")
      (node (ref "U11") (pin "88") (pinfunction "I/O_88") (pintype "bidirectional"))
    )
    (net (code "92") (name "/NVRAM_ADDRESS0") (class "Default")
      (node (ref "U11") (pin "129") (pinfunction "I/O_129") (pintype "bidirectional"))
    )
    (net (code "93") (name "/NVRAM_ADDRESS1") (class "Default")
      (node (ref "U11") (pin "128") (pinfunction "I/O_128") (pintype "bidirectional"))
    )
    (net (code "94") (name "/NVRAM_ADDRESS2") (class "Default")
      (node (ref "U11") (pin "126") (pinfunction "I/O_126") (pintype "bidirectional"))
    )
    (net (code "95") (name "/NVRAM_ADDRESS3") (class "Default")
      (node (ref "U11") (pin "124") (pinfunction "I/O_124") (pintype "bidirectional"))
    )
    (net (code "96") (name "/NVRAM_ADDRESS4") (class "Default")
      (node (ref "U11") (pin "123") (pinfunction "I/O_123") (pintype "bidirectional"))
    )
    (net (code "97") (name "/NVRAM_ADDRESS5") (class "Default")
      (node (ref "U11") (pin "122") (pinfunction "I/O_122") (pintype "bidirectional"))
    )
    (net (code "98") (name "/NVRAM_ADDRESS6") (class "Default")
      (node (ref "U11") (pin "121") (pinfunction "I/O_121") (pintype "bidirectional"))
    )
    (net (code "99") (name "/NVRAM_ADDRESS7") (class "Default")
      (node (ref "U11") (pin "120") (pinfunction "I/O_120") (pintype "bidirectional"))
    )
    (net (code "100") (name "/NVRAM_ADDRESS8") (class "Default")
      (node (ref "U11") (pin "119") (pinfunction "I/O_119") (pintype "bidirectional"))
    )
    (net (code "101") (name "/NVRAM_ADDRESS9") (class "Default")
      (node (ref "U11") (pin "102") (pinfunction "I/O_102") (pintype "bidirectional"))
    )
    (net (code "102") (name "/NVRAM_ADDRESS10") (class "Default")
      (node (ref "U11") (pin "101") (pinfunction "I/O_101") (pintype "bidirectional"))
    )
    (net (code "103") (name "/NVRAM_ADDRESS11") (class "Default")
      (node (ref "U11") (pin "100") (pinfunction "I/O_100") (pintype "bidirectional"))
    )
    (net (code "104") (name "/NVRAM_ADDRESS12") (class "Default")
      (node (ref "U11") (pin "99") (pinfunction "I/O_99") (pintype "bidirectional"))
    )
    (net (code "105") (name "/NVRAM_ADDRESS13") (class "Default")
      (node (ref "U11") (pin "98") (pinfunction "I/O_98") (pintype "bidirectional"))
    )
    (net (code "106") (name "/NVRAM_ADDRESS14") (class "Default")
      (node (ref "U11") (pin "97") (pinfunction "I/O_97") (pintype "bidirectional"))
    )
    (net (code "107") (name "/NVRAM_ADDRESS15") (class "Default")
      (node (ref "U11") (pin "96") (pinfunction "I/O_96") (pintype "bidirectional"))
    )
    (net (code "108") (name "/NVRAM_ADDRESS16") (class "Default")
      (node (ref "U11") (pin "95") (pinfunction "I/O_95") (pintype "bidirectional"))
    )
    (net (code "109") (name "/NVRAM_ADDRESS17") (class "Default")
      (node (ref "U11") (pin "93") (pinfunction "I/O_93") (pintype "bidirectional"))
    )
    (net (code "110") (name "/NVRAM_ADDRESS18") (class "Default")
      (node (ref "U11") (pin "92") (pinfunction "I/O_92") (pintype "bidirectional"))
    )
    (net (code "111") (name "/NVRAM_ADDRESS19") (class "Default")
      (node (ref "U11") (pin "91") (pinfunction "I/O_91") (pintype "bidirectional"))
    )
    (net (code "112") (name "/NVRAM_ADDRESS20") (class "Default")
      (node (ref "U11") (pin "90") (pinfunction "I/O_90") (pintype "bidirectional"))
    )
    (net (code "113") (name "/NVRAM_CE") (class "Default")
      (node (ref "U11") (pin "133") (pinfunction "I/O_133") (pintype "bidirectional"))
    )
    (net (code "114") (name "/NVRAM_DATA0") (class "Default")
      (node (ref "U11") (pin "188") (pinfunction "I/O_188") (pintype "bidirectional"))
    )
    (net (code "115") (name "/NVRAM_DATA1") (class "Default")
      (node (ref "U11") (pin "190") (pinfunction "I/O_190") (pintype "bidirectional"))
    )
    (net (code "116") (name "/NVRAM_DATA2") (class "Default")
      (node (ref "U11") (pin "192") (pinfunction "I/O_192") (pintype "bidirectional"))
    )
    (net (code "117") (name "/NVRAM_DATA3") (class "Default")
      (node (ref "U11") (pin "193") (pinfunction "I/O_193") (pintype "bidirectional"))
    )
    (net (code "118") (name "/NVRAM_DATA4") (class "Default")
      (node (ref "U11") (pin "194") (pinfunction "I/O_194") (pintype "bidirectional"))
    )
    (net (code "119") (name "/NVRAM_DATA5") (class "Default")
      (node (ref "U11") (pin "195") (pinfunction "I/O_195") (pintype "bidirectional"))
    )
    (net (code "120") (name "/NVRAM_DATA6") (class "Default")
      (node (ref "U11") (pin "196") (pinfunction "I/O_196") (pintype "bidirectional"))
    )
    (net (code "121") (name "/NVRAM_DATA7") (class "Default")
      (node (ref "U11") (pin "197") (pinfunction "I/O_197") (pintype "bidirectional"))
    )
    (net (code "122") (name "/NVRAM_OE") (class "Default")
      (node (ref "U11") (pin "136") (pinfunction "I/O_136") (pintype "bidirectional"))
    )
    (net (code "123") (name "/NVRAM_RST") (class "Default")
      (node (ref "U11") (pin "178") (pinfunction "I/O_178") (pintype "bidirectional"))
    )
    (net (code "124") (name "/NVRAM_WE") (class "Default")
      (node (ref "U11") (pin "137") (pinfunction "I/O_137") (pintype "bidirectional"))
    )
    (net (code "125") (name "/PPM_NOVI") (class "Default")
      (node (ref "U11") (pin "57") (pinfunction "I/O_57") (pintype "bidirectional"))
    )
    (net (code "126") (name "/PWR_GOOD_TPS") (class "Default")
      (node (ref "U11") (pin "149") (pinfunction "I/O_149") (pintype "bidirectional"))
    )
    (net (code "127") (name "/RESERVE1") (class "Default")
      (node (ref "U11") (pin "114") (pinfunction "I/O_114") (pintype "bidirectional"))
    )
    (net (code "128") (name "/RESERVE2") (class "Default")
      (node (ref "U11") (pin "115") (pinfunction "I/O_115") (pintype "bidirectional"))
    )
    (net (code "129") (name "/RESET_CPU") (class "Default")
      (node (ref "U11") (pin "111") (pinfunction "I/O_111") (pintype "bidirectional"))
    )
    (net (code "130") (name "/RES_DRV") (class "Default")
      (node (ref "S3") (pin "B2") (pinfunction "B2_B2") (pintype "passive"))
      (node (ref "U11") (pin "144") (pinfunction "I/O_144") (pintype "bidirectional"))
    )
    (net (code "131") (name "/RST_DOF_EN") (class "Default")
      (node (ref "J18") (pin "1") (pinfunction "1_1") (pintype "passive"))
      (node (ref "R30") (pin "1") (pinfunction "1_1") (pintype "passive"))
      (node (ref "U11") (pin "173") (pinfunction "I/O_173") (pintype "bidirectional"))
    )
    (net (code "132") (name "/SA0") (class "Default")
      (node (ref "S3") (pin "A31") (pinfunction "A31_A31") (pintype "passive"))
      (node (ref "U11") (pin "3") (pinfunction "I/O_3") (pintype "bidirectional"))
    )
    (net (code "133") (name "/SA1") (class "Default")
      (node (ref "S3") (pin "A30") (pinfunction "A30_A30") (pintype "passive"))
      (node (ref "U11") (pin "4") (pinfunction "I/O_4") (pintype "bidirectional"))
    )
    (net (code "134") (name "/SA2") (class "Default")
      (node (ref "S3") (pin "A29") (pinfunction "A29_A29") (pintype "passive"))
      (node (ref "U11") (pin "6") (pinfunction "I/O_6") (pintype "bidirectional"))
    )
    (net (code "135") (name "/SA3") (class "Default")
      (node (ref "S3") (pin "A28") (pinfunction "A28_A28") (pintype "passive"))
      (node (ref "U11") (pin "7") (pinfunction "I/O_7") (pintype "bidirectional"))
    )
    (net (code "136") (name "/SA4") (class "Default")
      (node (ref "S3") (pin "A27") (pinfunction "A27_A27") (pintype "passive"))
      (node (ref "U11") (pin "8") (pinfunction "I/O_8") (pintype "bidirectional"))
    )
    (net (code "137") (name "/SA5") (class "Default")
      (node (ref "S3") (pin "A26") (pinfunction "A26_A26") (pintype "passive"))
      (node (ref "U11") (pin "9") (pinfunction "I/O_9") (pintype "bidirectional"))
    )
    (net (code "138") (name "/SA6") (class "Default")
      (node (ref "S3") (pin "A25") (pinfunction "A25_A25") (pintype "passive"))
      (node (ref "U11") (pin "10") (pinfunction "I/O_10") (pintype "bidirectional"))
    )
    (net (code "139") (name "/SA7") (class "Default")
      (node (ref "S3") (pin "A24") (pinfunction "A24_A24") (pintype "passive"))
      (node (ref "U11") (pin "11") (pinfunction "I/O_11") (pintype "bidirectional"))
    )
    (net (code "140") (name "/SA8") (class "Default")
      (node (ref "S3") (pin "A23") (pinfunction "A23_A23") (pintype "passive"))
      (node (ref "U11") (pin "12") (pinfunction "I/O_12") (pintype "bidirectional"))
    )
    (net (code "141") (name "/SA9") (class "Default")
      (node (ref "S3") (pin "A22") (pinfunction "A22_A22") (pintype "passive"))
      (node (ref "U11") (pin "13") (pinfunction "I/O_13") (pintype "bidirectional"))
    )
    (net (code "142") (name "/SA10") (class "Default")
      (node (ref "S3") (pin "A21") (pinfunction "A21_A21") (pintype "passive"))
      (node (ref "U11") (pin "15") (pinfunction "I/O_15") (pintype "bidirectional"))
    )
    (net (code "143") (name "/SA11") (class "Default")
      (node (ref "S3") (pin "A20") (pinfunction "A20_A20") (pintype "passive"))
      (node (ref "U11") (pin "16") (pinfunction "I/O_16") (pintype "bidirectional"))
    )
    (net (code "144") (name "/SA12") (class "Default")
      (node (ref "S3") (pin "A19") (pinfunction "A19_A19") (pintype "passive"))
      (node (ref "U11") (pin "17") (pinfunction "I/O_17") (pintype "bidirectional"))
    )
    (net (code "145") (name "/SA13") (class "Default")
      (node (ref "S3") (pin "A18") (pinfunction "A18_A18") (pintype "passive"))
      (node (ref "U11") (pin "18") (pinfunction "I/O_18") (pintype "bidirectional"))
    )
    (net (code "146") (name "/SA14") (class "Default")
      (node (ref "S3") (pin "A17") (pinfunction "A17_A17") (pintype "passive"))
      (node (ref "U11") (pin "19") (pinfunction "I/O_19") (pintype "bidirectional"))
    )
    (net (code "147") (name "/SA15") (class "Default")
      (node (ref "S3") (pin "A16") (pinfunction "A16_A16") (pintype "passive"))
      (node (ref "U11") (pin "20") (pinfunction "I/O_20") (pintype "bidirectional"))
    )
    (net (code "148") (name "/SA16") (class "Default")
      (node (ref "S3") (pin "A15") (pinfunction "A15_A15") (pintype "passive"))
      (node (ref "U11") (pin "198") (pinfunction "I/O_198") (pintype "bidirectional"))
    )
    (net (code "149") (name "/SBHE") (class "Default")
      (node (ref "S3") (pin "C1") (pinfunction "C1_C1") (pintype "passive"))
      (node (ref "U11") (pin "187") (pinfunction "I/O_187") (pintype "bidirectional"))
    )
    (net (code "150") (name "/SMEMR") (class "Default")
      (node (ref "S3") (pin "B12") (pinfunction "B12_B12") (pintype "passive"))
      (node (ref "U11") (pin "138") (pinfunction "I/O_138") (pintype "bidirectional"))
    )
    (net (code "151") (name "/SMEMW") (class "Default")
      (node (ref "S3") (pin "B11") (pinfunction "B11_B11") (pintype "passive"))
      (node (ref "U11") (pin "139") (pinfunction "I/O_139") (pintype "bidirectional"))
    )
    (net (code "152") (name "/TCK") (class "Default")
      (node (ref "J14") (pin "6") (pinfunction "6_6") (pintype "passive"))
      (node (ref "RN12") (pin "6") (pinfunction "6_6") (pintype "passive"))
      (node (ref "U11") (pin "30") (pinfunction "TCK_30") (pintype "passive"))
    )
    (net (code "153") (name "/TDI") (class "Default")
      (node (ref "J14") (pin "10") (pinfunction "10_10") (pintype "passive"))
      (node (ref "RN12") (pin "8") (pinfunction "8_8") (pintype "passive"))
      (node (ref "U11") (pin "176") (pinfunction "TDI_176") (pintype "passive"))
    )
    (net (code "154") (name "/TDO") (class "Default")
      (node (ref "J14") (pin "8") (pinfunction "8_8") (pintype "passive"))
      (node (ref "RN12") (pin "7") (pinfunction "7_7") (pintype "passive"))
      (node (ref "U11") (pin "189") (pinfunction "TDO_189") (pintype "tri_state"))
    )
    (net (code "155") (name "/TMS") (class "Default")
      (node (ref "J14") (pin "4") (pinfunction "4_4") (pintype "passive"))
      (node (ref "RN12") (pin "5") (pinfunction "5_5") (pintype "passive"))
      (node (ref "U11") (pin "127") (pinfunction "TMS_127") (pintype "passive"))
    )
    (net (code "156") (name "/WDT_OUT_STARI") (class "Default")
      (node (ref "U11") (pin "56") (pinfunction "I/O_56") (pintype "bidirectional"))
    )
    (net (code "157") (name "/WDT_SIG_STARI") (class "Default")
      (node (ref "U11") (pin "68") (pinfunction "I/O_68") (pintype "bidirectional"))
    )
    (net (code "158") (name "/WDT_TRG") (class "Default")
      (node (ref "U11") (pin "55") (pinfunction "I/O_55") (pintype "bidirectional"))
    )
    (net (code "159") (name "/XP_PRESENT_IN") (class "Default")
      (node (ref "RN10") (pin "5") (pinfunction "5_5") (pintype "passive"))
      (node (ref "U11") (pin "89") (pinfunction "I/O_89") (pintype "bidirectional"))
    )
    (net (code "160") (name "/XP_PRESENT_OUT") (class "Default")
      (node (ref "S2") (pin "8") (pinfunction "A8_8") (pintype "passive"))
    )
    (net (code "161") (name "/{slash}FLTB1") (class "Default")
      (node (ref "U11") (pin "58") (pinfunction "I/O_58") (pintype "bidirectional"))
    )
    (net (code "162") (name "/{slash}NVRAM_RST") (class "Default")
      (node (ref "U11") (pin "140") (pinfunction "I/O_140") (pintype "bidirectional"))
    )
    (net (code "163") (name "GND") (class "Default")
      (node (ref "C14") (pin "2") (pinfunction "2_2") (pintype "passive"))
      (node (ref "C15") (pin "2") (pinfunction "2_2") (pintype "passive"))
      (node (ref "C16") (pin "2") (pinfunction "2_2") (pintype "passive"))
      (node (ref "C17") (pin "2") (pinfunction "2_2") (pintype "passive"))
      (node (ref "C18") (pin "2") (pinfunction "2_2") (pintype "passive"))
      (node (ref "C19") (pin "2") (pinfunction "2_2") (pintype "passive"))
      (node (ref "C20") (pin "2") (pinfunction "2_2") (pintype "passive"))
      (node (ref "C21") (pin "2") (pinfunction "2_2") (pintype "passive"))
      (node (ref "C22") (pin "2") (pinfunction "2_2") (pintype "passive"))
      (node (ref "C23") (pin "2") (pinfunction "2_2") (pintype "passive"))
      (node (ref "C24") (pin "2") (pinfunction "2_2") (pintype "passive"))
      (node (ref "C25") (pin "2") (pinfunction "2_2") (pintype "passive"))
      (node (ref "C26") (pin "2") (pinfunction "2_2") (pintype "passive"))
      (node (ref "C27") (pin "2") (pinfunction "2_2") (pintype "passive"))
      (node (ref "C28") (pin "2") (pinfunction "2_2") (pintype "passive"))
      (node (ref "C29") (pin "2") (pinfunction "2_2") (pintype "passive"))
      (node (ref "C30") (pin "2") (pinfunction "2_2") (pintype "passive"))
      (node (ref "C31") (pin "2") (pinfunction "2_2") (pintype "passive"))
      (node (ref "C32") (pin "2") (pinfunction "2_2") (pintype "passive"))
      (node (ref "C33") (pin "2") (pinfunction "2_2") (pintype "passive"))
      (node (ref "C34") (pin "2") (pinfunction "2_2") (pintype "passive"))
      (node (ref "C35") (pin "2") (pinfunction "2_2") (pintype "passive"))
      (node (ref "C36") (pin "2") (pinfunction "2_2") (pintype "passive"))
      (node (ref "C37") (pin "2") (pinfunction "2_2") (pintype "passive"))
      (node (ref "C38") (pin "2") (pinfunction "2_2") (pintype "passive"))
      (node (ref "C39") (pin "2") (pinfunction "2_2") (pintype "passive"))
      (node (ref "C40") (pin "2") (pinfunction "2_2") (pintype "passive"))
      (node (ref "C41") (pin "2") (pinfunction "2_2") (pintype "passive"))
      (node (ref "C42") (pin "2") (pinfunction "2_2") (pintype "passive"))
      (node (ref "C47") (pin "2") (pinfunction "2_2") (pintype "passive"))
      (node (ref "C48") (pin "2") (pinfunction "2_2") (pintype "passive"))
      (node (ref "C50") (pin "2") (pinfunction "2_2") (pintype "passive"))
      (node (ref "J11") (pin "2") (pinfunction "2_2") (pintype "passive"))
      (node (ref "J13") (pin "2") (pinfunction "2_2") (pintype "passive"))
      (node (ref "J14") (pin "1") (pinfunction "1_1") (pintype "passive"))
      (node (ref "J14") (pin "11") (pinfunction "11_11") (pintype "passive"))
      (node (ref "J14") (pin "13") (pinfunction "13_13") (pintype "passive"))
      (node (ref "J14") (pin "3") (pinfunction "3_3") (pintype "passive"))
      (node (ref "J14") (pin "5") (pinfunction "5_5") (pintype "passive"))
      (node (ref "J14") (pin "7") (pinfunction "7_7") (pintype "passive"))
      (node (ref "J14") (pin "9") (pinfunction "9_9") (pintype "passive"))
      (node (ref "J18") (pin "2") (pinfunction "2_2") (pintype "passive"))
      (node (ref "R23") (pin "2") (pinfunction "2_2") (pintype "passive"))
      (node (ref "S2") (pin "10") (pinfunction "B7_10") (pintype "passive"))
      (node (ref "S2") (pin "11") (pinfunction "B6_11") (pintype "passive"))
      (node (ref "S2") (pin "12") (pinfunction "B5_12") (pintype "passive"))
      (node (ref "S2") (pin "13") (pinfunction "B4_13") (pintype "passive"))
      (node (ref "S2") (pin "14") (pinfunction "B3_14") (pintype "passive"))
      (node (ref "S2") (pin "15") (pinfunction "B2_15") (pintype "passive"))
      (node (ref "S2") (pin "16") (pinfunction "B1_16") (pintype "passive"))
      (node (ref "S2") (pin "9") (pinfunction "B8_9") (pintype "passive"))
      (node (ref "S3") (pin "A32") (pinfunction "A32_A32") (pintype "passive"))
      (node (ref "S3") (pin "B1") (pinfunction "B1_B1") (pintype "passive"))
      (node (ref "S3") (pin "B10") (pinfunction "B10_B10") (pintype "passive"))
      (node (ref "S3") (pin "B31") (pinfunction "B31_B31") (pintype "passive"))
      (node (ref "S3") (pin "B32") (pinfunction "B32_B32") (pintype "passive"))
      (node (ref "S3") (pin "C0") (pinfunction "C0_C0") (pintype "passive"))
      (node (ref "S3") (pin "C19") (pinfunction "C19_C19") (pintype "passive"))
      (node (ref "S3") (pin "D0") (pinfunction "D0_D0") (pintype "passive"))
      (node (ref "S3") (pin "D18") (pinfunction "D18_D18") (pintype "passive"))
      (node (ref "S3") (pin "D19") (pinfunction "D19_D19") (pintype "passive"))
      (node (ref "STB1") (pin "2") (pinfunction "GND_2") (pintype "power_in"))
      (node (ref "STB1") (pin "4") (pinfunction "GND_4") (pintype "power_in"))
      (node (ref "U11") (pin "116") (pinfunction "PORT_EN_116") (pintype "passive"))
      (node (ref "U11") (pin "134") (pinfunction "GND_134") (pintype "power_in"))
      (node (ref "U11") (pin "14") (pinfunction "GND_14") (pintype "power_in"))
      (node (ref "U11") (pin "152") (pinfunction "GND_152") (pintype "power_in"))
      (node (ref "U11") (pin "174") (pinfunction "GND_174") (pintype "power_in"))
      (node (ref "U11") (pin "180") (pinfunction "GND_180") (pintype "power_in"))
      (node (ref "U11") (pin "185") (pinfunction "GND_185") (pintype "power_in"))
      (node (ref "U11") (pin "200") (pinfunction "GND_200") (pintype "power_in"))
      (node (ref "U11") (pin "32") (pinfunction "GND_32") (pintype "power_in"))
      (node (ref "U11") (pin "50") (pinfunction "GND_50") (pintype "power_in"))
      (node (ref "U11") (pin "72") (pinfunction "GND_72") (pintype "power_in"))
      (node (ref "U11") (pin "75") (pinfunction "GND_75") (pintype "power_in"))
      (node (ref "U11") (pin "82") (pinfunction "GND_82") (pintype "power_in"))
      (node (ref "U11") (pin "94") (pinfunction "GND_94") (pintype "power_in"))
      (node (ref "U12") (pin "2") (pinfunction "GND_2") (pintype "power_in"))
      (node (ref "U13") (pin "10") (pinfunction "K2_10") (pintype "passive"))
      (node (ref "U13") (pin "11") (pinfunction "K3_11") (pintype "passive"))
      (node (ref "U13") (pin "12") (pinfunction "K4_12") (pintype "passive"))
      (node (ref "U13") (pin "13") (pinfunction "K5_13") (pintype "passive"))
      (node (ref "U13") (pin "14") (pinfunction "K6_14") (pintype "passive"))
      (node (ref "U13") (pin "9") (pinfunction "K1_9") (pintype "passive"))
      (node (ref "U4") (pin "1") (pinfunction "1_1") (pintype "passive"))
    )
    (net (code "164") (name "Net-(U13-A1)") (class "Default")
      (node (ref "R17") (pin "1") (pinfunction "1_1") (pintype "passive"))
      (node (ref "U13") (pin "1") (pinfunction "A1_1") (pintype "passive"))
    )
    (net (code "165") (name "Net-(U13-A2)") (class "Default")
      (node (ref "R18") (pin "1") (pinfunction "1_1") (pintype "passive"))
      (node (ref "U13") (pin "2") (pinfunction "A2_2") (pintype "passive"))
    )
    (net (code "166") (name "Net-(U13-A3)") (class "Default")
      (node (ref "R19") (pin "1") (pinfunction "1_1") (pintype "passive"))
      (node (ref "U13") (pin "3") (pinfunction "A3_3") (pintype "passive"))
    )
    (net (code "167") (name "Net-(U13-A4)") (class "Default")
      (node (ref "R20") (pin "1") (pinfunction "1_1") (pintype "passive"))
      (node (ref "U13") (pin "4") (pinfunction "A4_4") (pintype "passive"))
    )
    (net (code "168") (name "Net-(U13-A5)") (class "Default")
      (node (ref "R21") (pin "1") (pinfunction "1_1") (pintype "passive"))
      (node (ref "U13") (pin "5") (pinfunction "A5_5") (pintype "passive"))
    )
    (net (code "169") (name "Net-(U13-A6)") (class "Default")
      (node (ref "R22") (pin "1") (pinfunction "1_1") (pintype "passive"))
      (node (ref "U13") (pin "6") (pinfunction "A6_6") (pintype "passive"))
    )
    (net (code "170") (name "Net-(U13-K7)") (class "Default")
      (node (ref "R23") (pin "1") (pinfunction "1_1") (pintype "passive"))
      (node (ref "U13") (pin "15") (pinfunction "K7_15") (pintype "passive"))
    )
    (net (code "171") (name "Net-(U13-K8)") (class "Default")
      (node (ref "R24") (pin "1") (pinfunction "1_1") (pintype "passive"))
      (node (ref "U13") (pin "16") (pinfunction "K8_16") (pintype "passive"))
    )
    (net (code "172") (name "VCC_+5V") (class "Default")
      (node (ref "C42") (pin "1") (pinfunction "1_1") (pintype "passive"))
      (node (ref "D4") (pin "2") (pinfunction "CATHODE_2") (pintype "passive"))
      (node (ref "S3") (pin "B29") (pinfunction "B29_B29") (pintype "passive"))
      (node (ref "S3") (pin "B3") (pinfunction "B3_B3") (pintype "passive"))
      (node (ref "S3") (pin "D16") (pinfunction "D16_D16") (pintype "passive"))
      (node (ref "STB1") (pin "1") (pinfunction "IN_1") (pintype "power_in"))
      (node (ref "U13") (pin "7") (pinfunction "A7_7") (pintype "passive"))
      (node (ref "UR3") (pin "1") (pinfunction "1_1") (pintype "power_in"))
      (node (ref "UR4") (pin "1") (pinfunction "1_1") (pintype "power_in"))
    )
    (net (code "173") (name "VCC_+12V") (class "Default")
      (node (ref "U13") (pin "8") (pinfunction "A8_8") (pintype "passive"))
    )
    (net (code "174") (name "VCC_-12V") (class "Default")
      (node (ref "R24") (pin "2") (pinfunction "2_2") (pintype "passive"))
    )
    (net (code "175") (name "VCC_3V3") (class "Default")
      (node (ref "C14") (pin "1") (pinfunction "1_1") (pintype "passive"))
      (node (ref "C15") (pin "1") (pinfunction "1_1") (pintype "passive"))
      (node (ref "C16") (pin "1") (pinfunction "1_1") (pintype "passive"))
      (node (ref "C17") (pin "1") (pinfunction "1_1") (pintype "passive"))
      (node (ref "C18") (pin "1") (pinfunction "1_1") (pintype "passive"))
      (node (ref "C19") (pin "1") (pinfunction "1_1") (pintype "passive"))
      (node (ref "C20") (pin "1") (pinfunction "1_1") (pintype "passive"))
      (node (ref "C21") (pin "1") (pinfunction "1_1") (pintype "passive"))
      (node (ref "C22") (pin "1") (pinfunction "1_1") (pintype "passive"))
      (node (ref "C23") (pin "1") (pinfunction "1_1") (pintype "passive"))
      (node (ref "C24") (pin "1") (pinfunction "1_1") (pintype "passive"))
      (node (ref "C25") (pin "1") (pinfunction "1_1") (pintype "passive"))
      (node (ref "C26") (pin "1") (pinfunction "1_1") (pintype "passive"))
      (node (ref "C27") (pin "1") (pinfunction "1_1") (pintype "passive"))
      (node (ref "C28") (pin "1") (pinfunction "1_1") (pintype "passive"))
      (node (ref "C29") (pin "1") (pinfunction "1_1") (pintype "passive"))
      (node (ref "C30") (pin "1") (pinfunction "1_1") (pintype "passive"))
      (node (ref "C31") (pin "1") (pinfunction "1_1") (pintype "passive"))
      (node (ref "C32") (pin "1") (pinfunction "1_1") (pintype "passive"))
      (node (ref "C33") (pin "1") (pinfunction "1_1") (pintype "passive"))
      (node (ref "C34") (pin "1") (pinfunction "1_1") (pintype "passive"))
      (node (ref "C35") (pin "1") (pinfunction "1_1") (pintype "passive"))
      (node (ref "C36") (pin "1") (pinfunction "1_1") (pintype "passive"))
      (node (ref "C37") (pin "1") (pinfunction "1_1") (pintype "passive"))
      (node (ref "C38") (pin "1") (pinfunction "1_1") (pintype "passive"))
      (node (ref "C39") (pin "1") (pinfunction "1_1") (pintype "passive"))
      (node (ref "C40") (pin "1") (pinfunction "1_1") (pintype "passive"))
      (node (ref "C41") (pin "1") (pinfunction "1_1") (pintype "passive"))
      (node (ref "C47") (pin "1") (pinfunction "1_1") (pintype "passive"))
      (node (ref "C48") (pin "1") (pinfunction "1_1") (pintype "passive"))
      (node (ref "C50") (pin "1") (pinfunction "1_1") (pintype "passive"))
      (node (ref "D4") (pin "1") (pinfunction "ANODE_1") (pintype "passive"))
      (node (ref "J14") (pin "2") (pinfunction "2_2") (pintype "passive"))
      (node (ref "R30") (pin "2") (pinfunction "2_2") (pintype "passive"))
      (node (ref "RN10") (pin "1") (pinfunction "1_1") (pintype "passive"))
      (node (ref "RN10") (pin "2") (pinfunction "2_2") (pintype "passive"))
      (node (ref "RN10") (pin "3") (pinfunction "3_3") (pintype "passive"))
      (node (ref "RN10") (pin "4") (pinfunction "4_4") (pintype "passive"))
      (node (ref "RN11") (pin "1") (pinfunction "1_1") (pintype "passive"))
      (node (ref "RN11") (pin "2") (pinfunction "2_2") (pintype "passive"))
      (node (ref "RN11") (pin "3") (pinfunction "3_3") (pintype "passive"))
      (node (ref "RN11") (pin "4") (pinfunction "4_4") (pintype "passive"))
      (node (ref "RN12") (pin "1") (pinfunction "1_1") (pintype "passive"))
      (node (ref "RN12") (pin "2") (pinfunction "2_2") (pintype "passive"))
      (node (ref "RN12") (pin "3") (pinfunction "3_3") (pintype "passive"))
      (node (ref "RN12") (pin "4") (pinfunction "4_4") (pintype "passive"))
      (node (ref "RN13") (pin "1") (pinfunction "1_1") (pintype "passive"))
      (node (ref "RN13") (pin "2") (pinfunction "2_2") (pintype "passive"))
      (node (ref "RN13") (pin "3") (pinfunction "3_3") (pintype "passive"))
      (node (ref "RN13") (pin "4") (pinfunction "4_4") (pintype "passive"))
      (node (ref "RN14") (pin "1") (pinfunction "1_1") (pintype "passive"))
      (node (ref "RN14") (pin "2") (pinfunction "2_2") (pintype "passive"))
      (node (ref "RN14") (pin "3") (pinfunction "3_3") (pintype "passive"))
      (node (ref "RN14") (pin "4") (pinfunction "4_4") (pintype "passive"))
      (node (ref "STB1") (pin "3") (pinfunction "OUT_3") (pintype "power_in"))
      (node (ref "U11") (pin "107") (pinfunction "VCC_107") (pintype "power_in"))
      (node (ref "U11") (pin "125") (pinfunction "VCC_125") (pintype "power_in"))
      (node (ref "U11") (pin "143") (pinfunction "VCC_143") (pintype "power_in"))
      (node (ref "U11") (pin "165") (pinfunction "VCC_165") (pintype "power_in"))
      (node (ref "U11") (pin "179") (pinfunction "VCC_179") (pintype "power_in"))
      (node (ref "U11") (pin "186") (pinfunction "VCC_186") (pintype "power_in"))
      (node (ref "U11") (pin "191") (pinfunction "VCC_191") (pintype "power_in"))
      (node (ref "U11") (pin "23") (pinfunction "VCC_23") (pintype "power_in"))
      (node (ref "U11") (pin "41") (pinfunction "VCC_41") (pintype "power_in"))
      (node (ref "U11") (pin "5") (pinfunction "VCC_5") (pintype "power_in"))
      (node (ref "U11") (pin "63") (pinfunction "VCC_63") (pintype "power_in"))
      (node (ref "U11") (pin "74") (pinfunction "VCC_74") (pintype "power_in"))
      (node (ref "U11") (pin "83") (pinfunction "VCC_83") (pintype "power_in"))
      (node (ref "U11") (pin "85") (pinfunction "VCC_85") (pintype "power_in"))
      (node (ref "U12") (pin "4") (pinfunction "VDD_4") (pintype "power_in"))
      (node (ref "UR1") (pin "1") (pinfunction "1_1") (pintype "power_in"))
      (node (ref "UR2") (pin "1") (pinfunction "1_1") (pintype "power_in"))
    )
    (net (code "176") (name "unconnected-(J14-Pad12)") (class "Default")
      (node (ref "J14") (pin "12") (pinfunction "12_12") (pintype "passive"))
    )
    (net (code "177") (name "unconnected-(J14-Pad14)") (class "Default")
      (node (ref "J14") (pin "14") (pinfunction "14_14") (pintype "passive"))
    )
    (net (code "178") (name "unconnected-(J14-Pad15)") (class "Default")
      (node (ref "J14") (pin "15") (pinfunction "15_15") (pintype "passive"))
    )
    (net (code "179") (name "unconnected-(J14-Pad16)") (class "Default")
      (node (ref "J14") (pin "16") (pinfunction "16_16") (pintype "passive"))
    )
    (net (code "180") (name "unconnected-(RN10-Pad6)") (class "Default")
      (node (ref "RN10") (pin "6") (pinfunction "6_6") (pintype "passive"))
    )
    (net (code "181") (name "unconnected-(RN13-Pad8)") (class "Default")
      (node (ref "RN13") (pin "8") (pinfunction "8_8") (pintype "passive"))
    )
    (net (code "182") (name "unconnected-(RN14-Pad8)") (class "Default")
      (node (ref "RN14") (pin "8") (pinfunction "8_8") (pintype "passive"))
    )
    (net (code "183") (name "unconnected-(S2-A7-Pad7)") (class "Default")
      (node (ref "S2") (pin "7") (pinfunction "A7_7") (pintype "passive"))
    )
    (net (code "184") (name "unconnected-(S3-PadA1)") (class "Default")
      (node (ref "S3") (pin "A1") (pinfunction "A1_A1") (pintype "passive"))
    )
    (net (code "185") (name "unconnected-(S3-PadA10)") (class "Default")
      (node (ref "S3") (pin "A10") (pinfunction "A10_A10") (pintype "passive"))
    )
    (net (code "186") (name "unconnected-(S3-PadB5)") (class "Default")
      (node (ref "S3") (pin "B5") (pinfunction "B5_B5") (pintype "passive"))
    )
    (net (code "187") (name "unconnected-(S3-PadB6)") (class "Default")
      (node (ref "S3") (pin "B6") (pinfunction "B6_B6") (pintype "passive"))
    )
    (net (code "188") (name "unconnected-(S3-PadB7)") (class "Default")
      (node (ref "S3") (pin "B7") (pinfunction "B7_B7") (pintype "passive"))
    )
    (net (code "189") (name "unconnected-(S3-PadB8)") (class "Default")
      (node (ref "S3") (pin "B8") (pinfunction "B8_B8") (pintype "passive"))
    )
    (net (code "190") (name "unconnected-(S3-PadB9)") (class "Default")
      (node (ref "S3") (pin "B9") (pinfunction "B9_B9") (pintype "passive"))
    )
    (net (code "191") (name "unconnected-(S3-PadB15)") (class "Default")
      (node (ref "S3") (pin "B15") (pinfunction "B15_B15") (pintype "passive"))
    )
    (net (code "192") (name "unconnected-(S3-PadB16)") (class "Default")
      (node (ref "S3") (pin "B16") (pinfunction "B16_B16") (pintype "passive"))
    )
    (net (code "193") (name "unconnected-(S3-PadB17)") (class "Default")
      (node (ref "S3") (pin "B17") (pinfunction "B17_B17") (pintype "passive"))
    )
    (net (code "194") (name "unconnected-(S3-PadB18)") (class "Default")
      (node (ref "S3") (pin "B18") (pinfunction "B18_B18") (pintype "passive"))
    )
    (net (code "195") (name "unconnected-(S3-PadB19)") (class "Default")
      (node (ref "S3") (pin "B19") (pinfunction "B19_B19") (pintype "passive"))
    )
    (net (code "196") (name "unconnected-(S3-PadB20)") (class "Default")
      (node (ref "S3") (pin "B20") (pinfunction "B20_B20") (pintype "passive"))
    )
    (net (code "197") (name "unconnected-(S3-PadB21)") (class "Default")
      (node (ref "S3") (pin "B21") (pinfunction "B21_B21") (pintype "passive"))
    )
    (net (code "198") (name "unconnected-(S3-PadB22)") (class "Default")
      (node (ref "S3") (pin "B22") (pinfunction "B22_B22") (pintype "passive"))
    )
    (net (code "199") (name "unconnected-(S3-PadB23)") (class "Default")
      (node (ref "S3") (pin "B23") (pinfunction "B23_B23") (pintype "passive"))
    )
    (net (code "200") (name "unconnected-(S3-PadB24)") (class "Default")
      (node (ref "S3") (pin "B24") (pinfunction "B24_B24") (pintype "passive"))
    )
    (net (code "201") (name "unconnected-(S3-PadB25)") (class "Default")
      (node (ref "S3") (pin "B25") (pinfunction "B25_B25") (pintype "passive"))
    )
    (net (code "202") (name "unconnected-(S3-PadB26)") (class "Default")
      (node (ref "S3") (pin "B26") (pinfunction "B26_B26") (pintype "passive"))
    )
    (net (code "203") (name "unconnected-(S3-PadB27)") (class "Default")
      (node (ref "S3") (pin "B27") (pinfunction "B27_B27") (pintype "passive"))
    )
    (net (code "204") (name "unconnected-(S3-PadB30)") (class "Default")
      (node (ref "S3") (pin "B30") (pinfunction "B30_B30") (pintype "passive"))
    )
    (net (code "205") (name "unconnected-(S3-PadC6)") (class "Default")
      (node (ref "S3") (pin "C6") (pinfunction "C6_C6") (pintype "passive"))
    )
    (net (code "206") (name "unconnected-(S3-PadC7)") (class "Default")
      (node (ref "S3") (pin "C7") (pinfunction "C7_C7") (pintype "passive"))
    )
    (net (code "207") (name "unconnected-(S3-PadC8)") (class "Default")
      (node (ref "S3") (pin "C8") (pinfunction "C8_C8") (pintype "passive"))
    )
    (net (code "208") (name "unconnected-(S3-PadC9)") (class "Default")
      (node (ref "S3") (pin "C9") (pinfunction "C9_C9") (pintype "passive"))
    )
    (net (code "209") (name "unconnected-(S3-PadC10)") (class "Default")
      (node (ref "S3") (pin "C10") (pinfunction "C10_C10") (pintype "passive"))
    )
    (net (code "210") (name "unconnected-(S3-PadD1)") (class "Default")
      (node (ref "S3") (pin "D1") (pinfunction "D1_D1") (pintype "passive"))
    )
    (net (code "211") (name "unconnected-(S3-PadD8)") (class "Default")
      (node (ref "S3") (pin "D8") (pinfunction "D8_D8") (pintype "passive"))
    )
    (net (code "212") (name "unconnected-(S3-PadD9)") (class "Default")
      (node (ref "S3") (pin "D9") (pinfunction "D9_D9") (pintype "passive"))
    )
    (net (code "213") (name "unconnected-(S3-PadD10)") (class "Default")
      (node (ref "S3") (pin "D10") (pinfunction "D10_D10") (pintype "passive"))
    )
    (net (code "214") (name "unconnected-(S3-PadD11)") (class "Default")
      (node (ref "S3") (pin "D11") (pinfunction "D11_D11") (pintype "passive"))
    )
    (net (code "215") (name "unconnected-(S3-PadD12)") (class "Default")
      (node (ref "S3") (pin "D12") (pinfunction "D12_D12") (pintype "passive"))
    )
    (net (code "216") (name "unconnected-(S3-PadD13)") (class "Default")
      (node (ref "S3") (pin "D13") (pinfunction "D13_D13") (pintype "passive"))
    )
    (net (code "217") (name "unconnected-(S3-PadD14)") (class "Default")
      (node (ref "S3") (pin "D14") (pinfunction "D14_D14") (pintype "passive"))
    )
    (net (code "218") (name "unconnected-(S3-PadD15)") (class "Default")
      (node (ref "S3") (pin "D15") (pinfunction "D15_D15") (pintype "passive"))
    )
    (net (code "219") (name "unconnected-(S3-PadD17)") (class "Default")
      (node (ref "S3") (pin "D17") (pinfunction "D17_D17") (pintype "passive"))
    )
    (net (code "220") (name "unconnected-(U5-Pad1)") (class "Default")
      (node (ref "U5") (pin "1") (pinfunction "1_1") (pintype "passive"))
    )
    (net (code "221") (name "unconnected-(U11-I{slash}O-Pad24)") (class "Default")
      (node (ref "U11") (pin "24") (pinfunction "I/O_24") (pintype "bidirectional"))
    )
    (net (code "222") (name "unconnected-(U11-I{slash}O-Pad27)") (class "Default")
      (node (ref "U11") (pin "27") (pinfunction "I/O_27") (pintype "bidirectional"))
    )
    (net (code "223") (name "unconnected-(U11-I{slash}O-Pad135)") (class "Default")
      (node (ref "U11") (pin "135") (pinfunction "I/O_135") (pintype "bidirectional"))
    )
    (net (code "224") (name "unconnected-(U11-I{slash}O-Pad146)") (class "Default")
      (node (ref "U11") (pin "146") (pinfunction "I/O_146") (pintype "bidirectional"))
    )
    (net (code "225") (name "unconnected-(U11-I{slash}O-Pad166)") (class "Default")
      (node (ref "U11") (pin "166") (pinfunction "I/O_166") (pintype "bidirectional"))
    )
    (net (code "226") (name "unconnected-(U11-I{slash}O-Pad167)") (class "Default")
      (node (ref "U11") (pin "167") (pinfunction "I/O_167") (pintype "bidirectional"))
    )
    (net (code "227") (name "unconnected-(U11-I{slash}O-Pad171)") (class "Default")
      (node (ref "U11") (pin "171") (pinfunction "I/O_171") (pintype "bidirectional"))
    )
    (net (code "228") (name "unconnected-(U11-I{slash}O-Pad172)") (class "Default")
      (node (ref "U11") (pin "172") (pinfunction "I/O_172") (pintype "bidirectional"))
    )
    (net (code "229") (name "unconnected-(U11-I{slash}O-Pad175)") (class "Default")
      (node (ref "U11") (pin "175") (pinfunction "I/O_175") (pintype "bidirectional"))
    )
    (net (code "230") (name "unconnected-(U11-I{slash}O-Pad177)") (class "Default")
      (node (ref "U11") (pin "177") (pinfunction "I/O_177") (pintype "bidirectional"))
    )
    (net (code "231") (name "unconnected-(U11-NC-Pad1)") (class "Default")
      (node (ref "U11") (pin "1") (pinfunction "NC_1") (pintype "bidirectional"))
    )
    (net (code "232") (name "unconnected-(U11-NC-Pad2)") (class "Default")
      (node (ref "U11") (pin "2") (pinfunction "NC_2") (pintype "bidirectional"))
    )
    (net (code "233") (name "unconnected-(U11-NC-Pad51)") (class "Default")
      (node (ref "U11") (pin "51") (pinfunction "NC_51") (pintype "bidirectional"))
    )
    (net (code "234") (name "unconnected-(U11-NC-Pad52)") (class "Default")
      (node (ref "U11") (pin "52") (pinfunction "NC_52") (pintype "bidirectional"))
    )
    (net (code "235") (name "unconnected-(U11-NC-Pad53)") (class "Default")
      (node (ref "U11") (pin "53") (pinfunction "NC_53") (pintype "bidirectional"))
    )
    (net (code "236") (name "unconnected-(U11-NC-Pad54)") (class "Default")
      (node (ref "U11") (pin "54") (pinfunction "NC_54") (pintype "bidirectional"))
    )
    (net (code "237") (name "unconnected-(U11-NC-Pad103)") (class "Default")
      (node (ref "U11") (pin "103") (pinfunction "NC_103") (pintype "bidirectional"))
    )
    (net (code "238") (name "unconnected-(U11-NC-Pad104)") (class "Default")
      (node (ref "U11") (pin "104") (pinfunction "NC_104") (pintype "bidirectional"))
    )
    (net (code "239") (name "unconnected-(U11-NC-Pad105)") (class "Default")
      (node (ref "U11") (pin "105") (pinfunction "NC_105") (pintype "bidirectional"))
    )
    (net (code "240") (name "unconnected-(U11-NC-Pad106)") (class "Default")
      (node (ref "U11") (pin "106") (pinfunction "NC_106") (pintype "bidirectional"))
    )
    (net (code "241") (name "unconnected-(U11-NC-Pad155)") (class "Default")
      (node (ref "U11") (pin "155") (pinfunction "NC_155") (pintype "bidirectional"))
    )
    (net (code "242") (name "unconnected-(U11-NC-Pad156)") (class "Default")
      (node (ref "U11") (pin "156") (pinfunction "NC_156") (pintype "bidirectional"))
    )
    (net (code "243") (name "unconnected-(U11-NC-Pad157)") (class "Default")
      (node (ref "U11") (pin "157") (pinfunction "NC_157") (pintype "bidirectional"))
    )
    (net (code "244") (name "unconnected-(U11-NC-Pad158)") (class "Default")
      (node (ref "U11") (pin "158") (pinfunction "NC_158") (pintype "bidirectional"))
    )
    (net (code "245") (name "unconnected-(U11-NC-Pad207)") (class "Default")
      (node (ref "U11") (pin "207") (pinfunction "NC_207") (pintype "bidirectional"))
    )
    (net (code "246") (name "unconnected-(U11-NC-Pad208)") (class "Default")
      (node (ref "U11") (pin "208") (pinfunction "NC_208") (pintype "bidirectional"))
    )
    (net (code "247") (name "unconnected-(UR5-Pad1)") (class "Default")
      (node (ref "UR5") (pin "1") (pinfunction "1_1") (pintype "passive"))
    )
    (net (code "248") (name "unconnected-(UR6-Pad1)") (class "Default")
      (node (ref "UR6") (pin "1") (pinfunction "1_1") (pintype "passive"))
    )
    (net (code "249") (name "unconnected-(UR7-Pad1)") (class "Default")
      (node (ref "UR7") (pin "1") (pinfunction "1_1") (pintype "passive"))
    )
    (net (code "250") (name "unconnected-(UR8-Pad1)") (class "Default")
      (node (ref "UR8") (pin "1") (pinfunction "1_1") (pintype "passive"))
    )
    (net (code "251") (name "unconnected-(UR9-Pad1)") (class "Default")
      (node (ref "UR9") (pin "1") (pinfunction "1_1") (pintype "passive"))
    )
    (net (code "252") (name "unconnected-(UR10-Pad1)") (class "Default")
      (node (ref "UR10") (pin "1") (pinfunction "1_1") (pintype "passive"))
    )
    (net (code "253") (name "unconnected-(UR11-Pad1)") (class "Default")
      (node (ref "UR11") (pin "1") (pinfunction "1_1") (pintype "passive"))
    )
    (net (code "254") (name "unconnected-(UR12-Pad1)") (class "Default")
      (node (ref "UR12") (pin "1") (pinfunction "1_1") (pintype "passive"))
    )
  )
)
